# SniperBoard.net
KiCad netlist of a schematic drawn in EAGLE
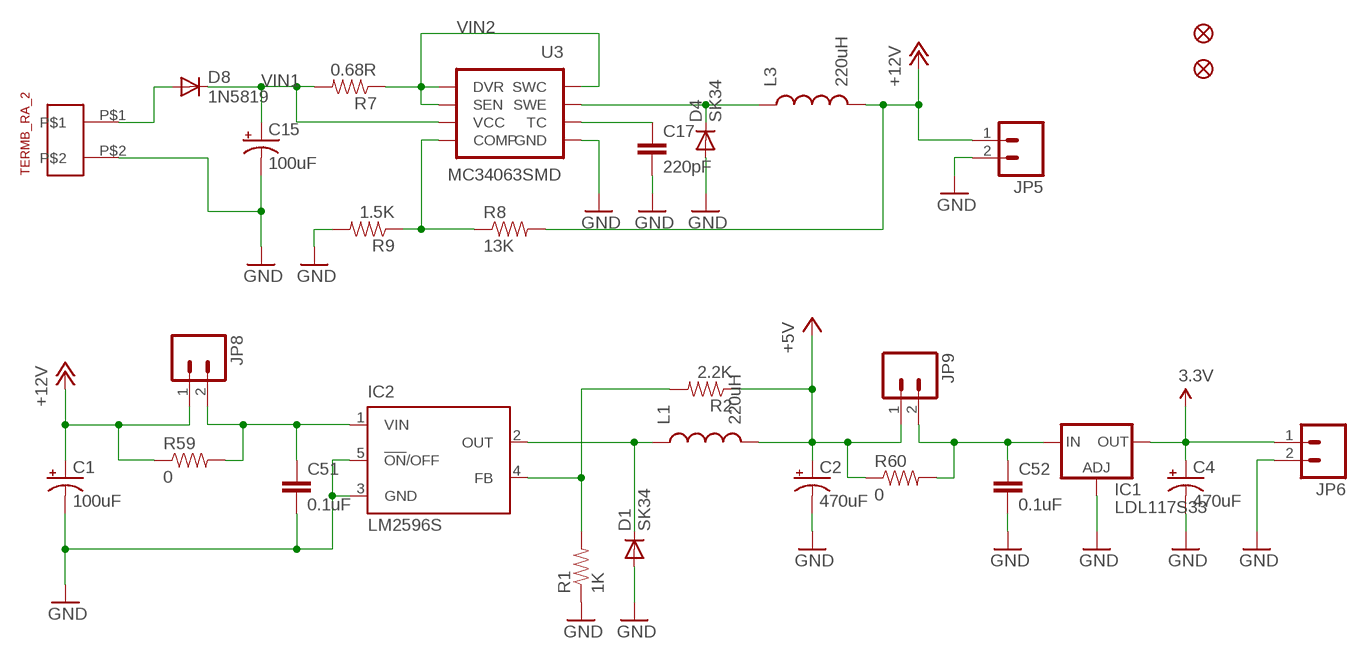
[diagram p0: schematic, sheet 1]
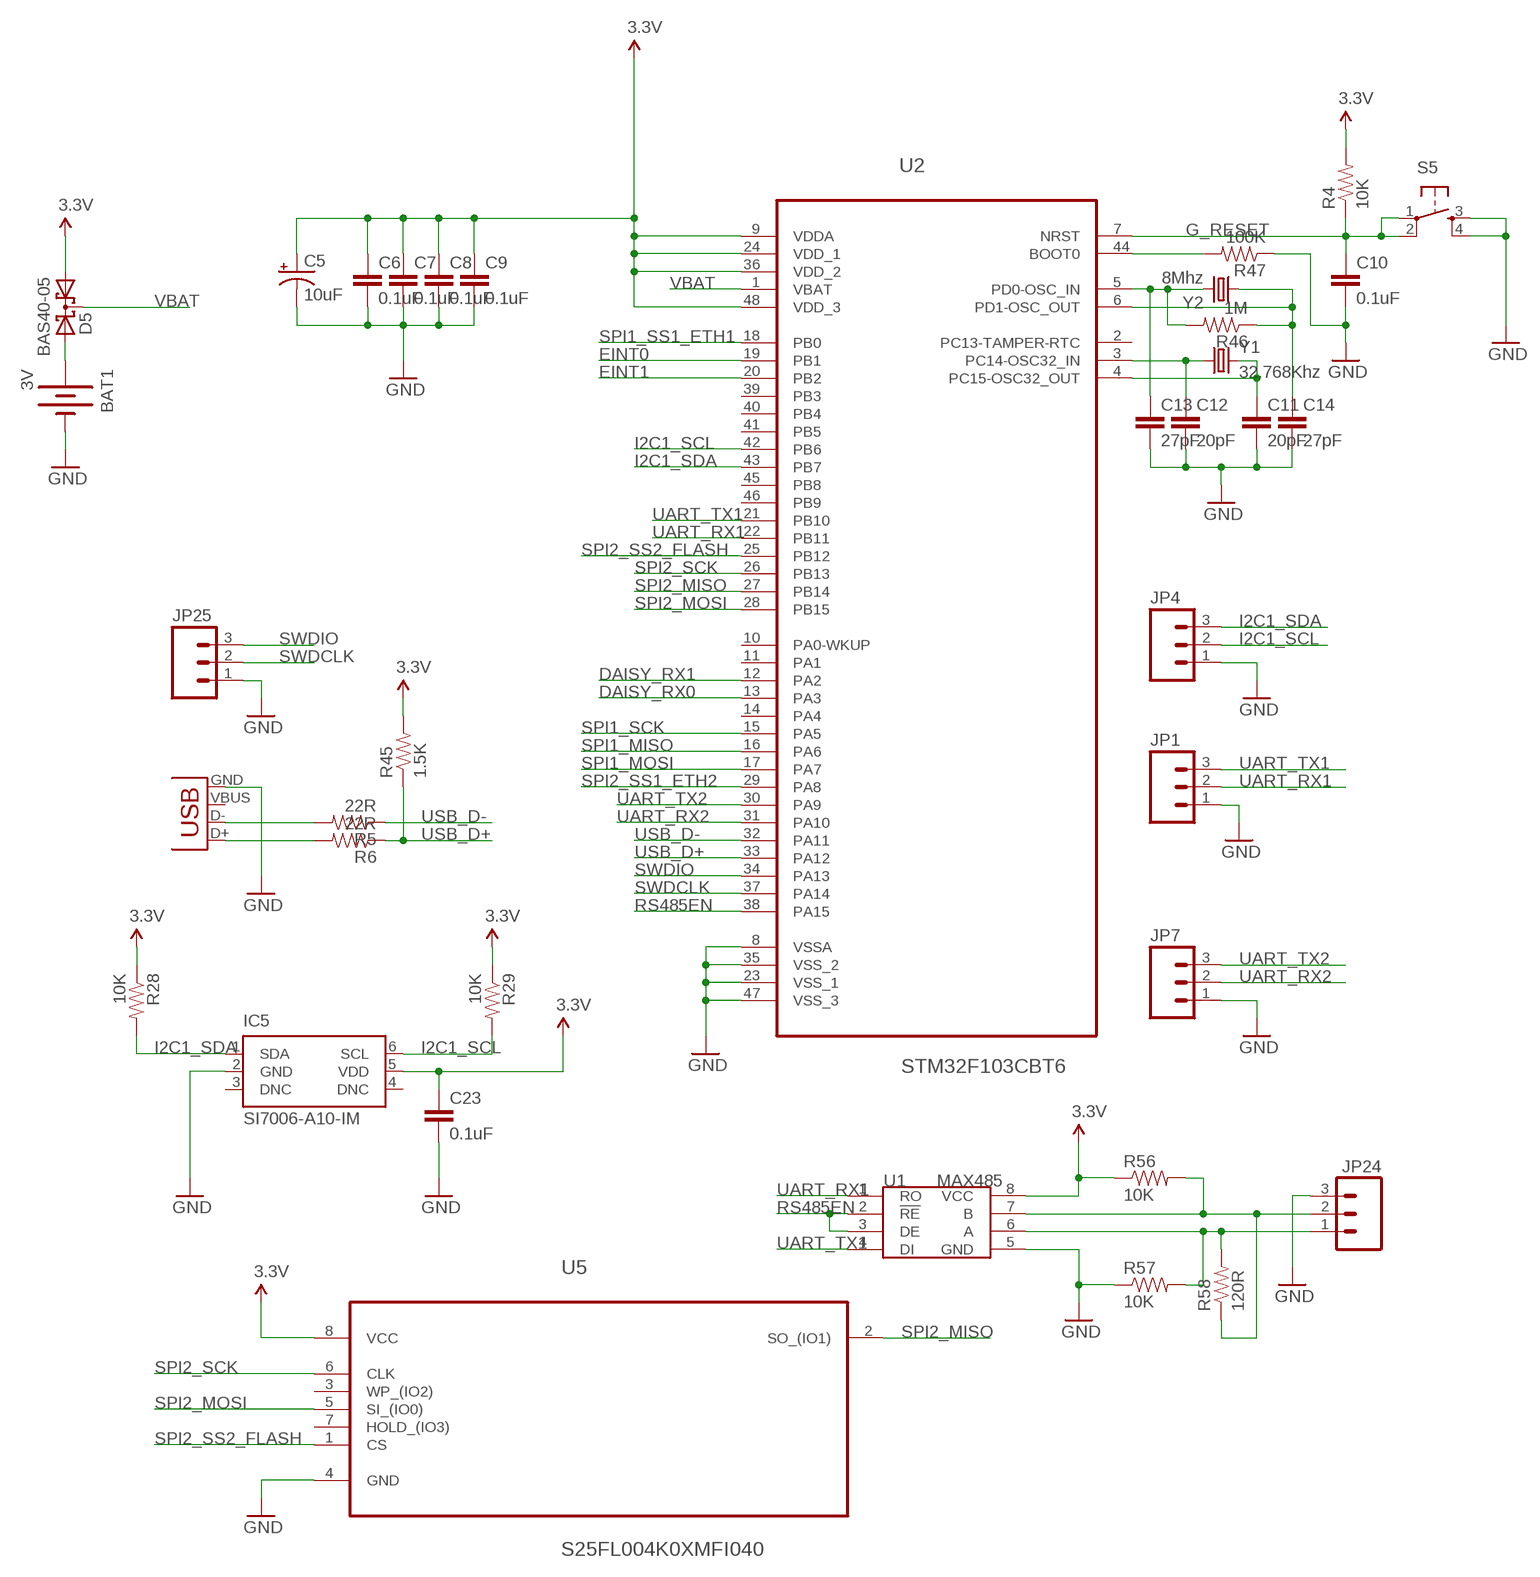
[diagram p1: schematic, sheet 2]
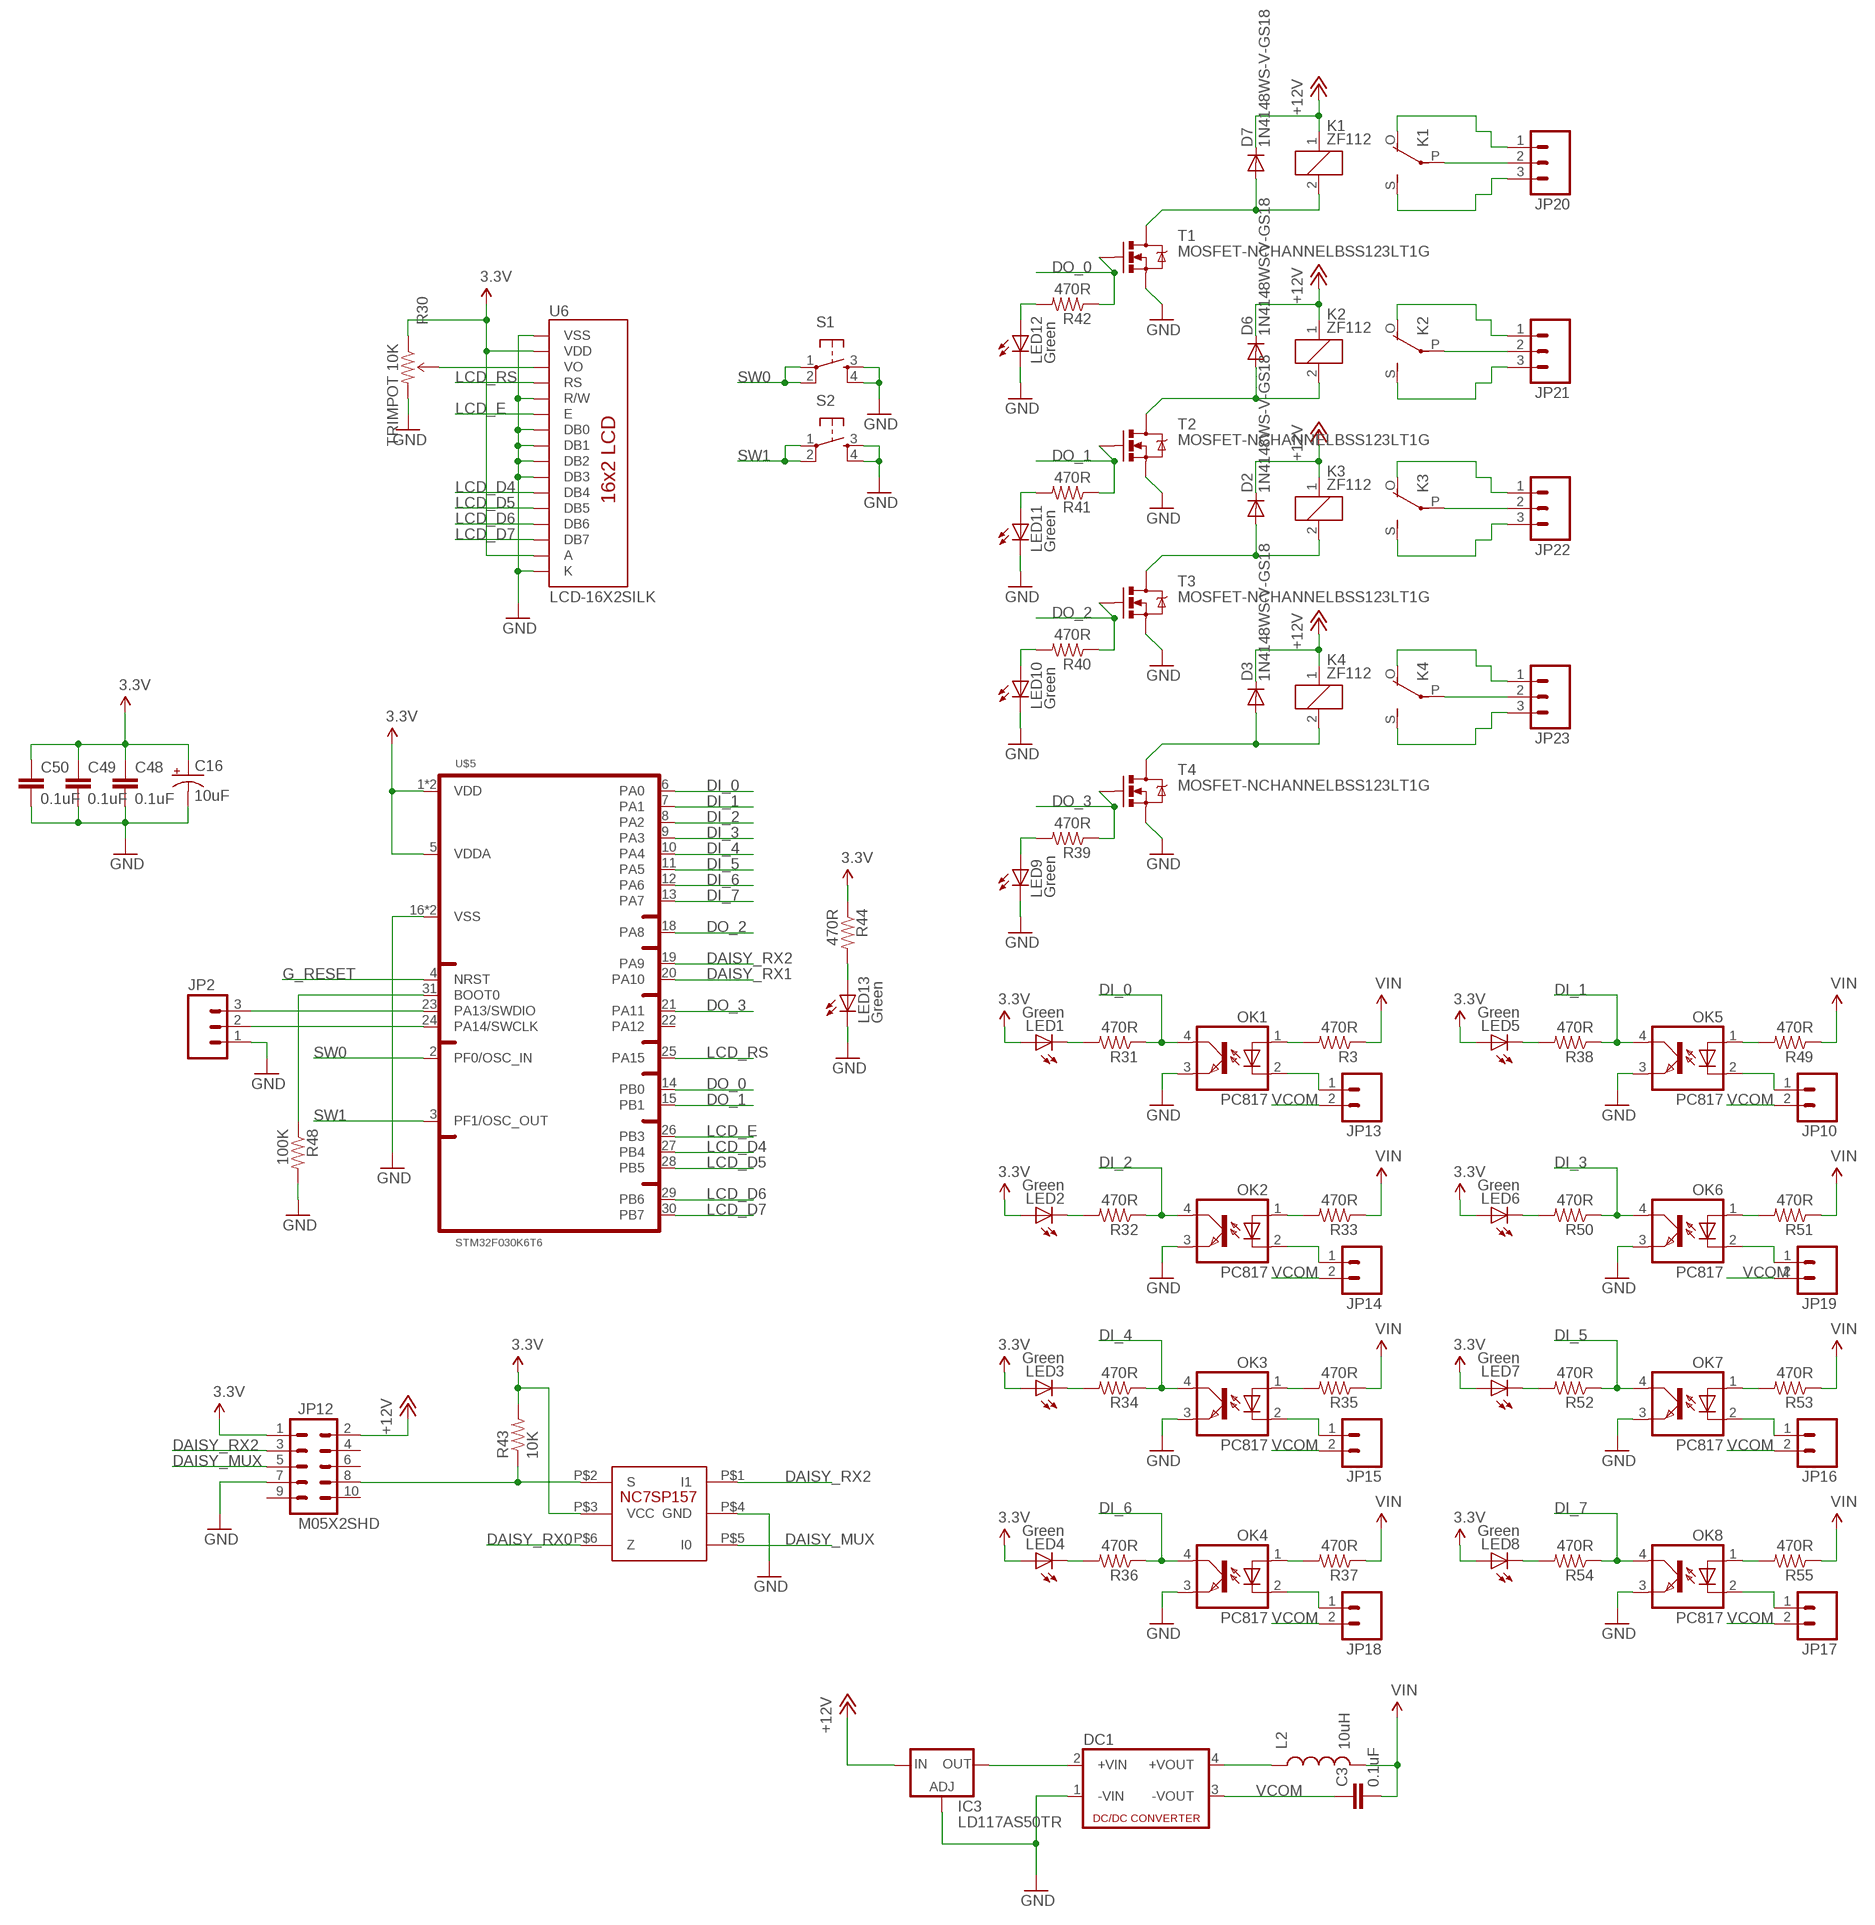
[diagram p2: schematic, sheet 3]
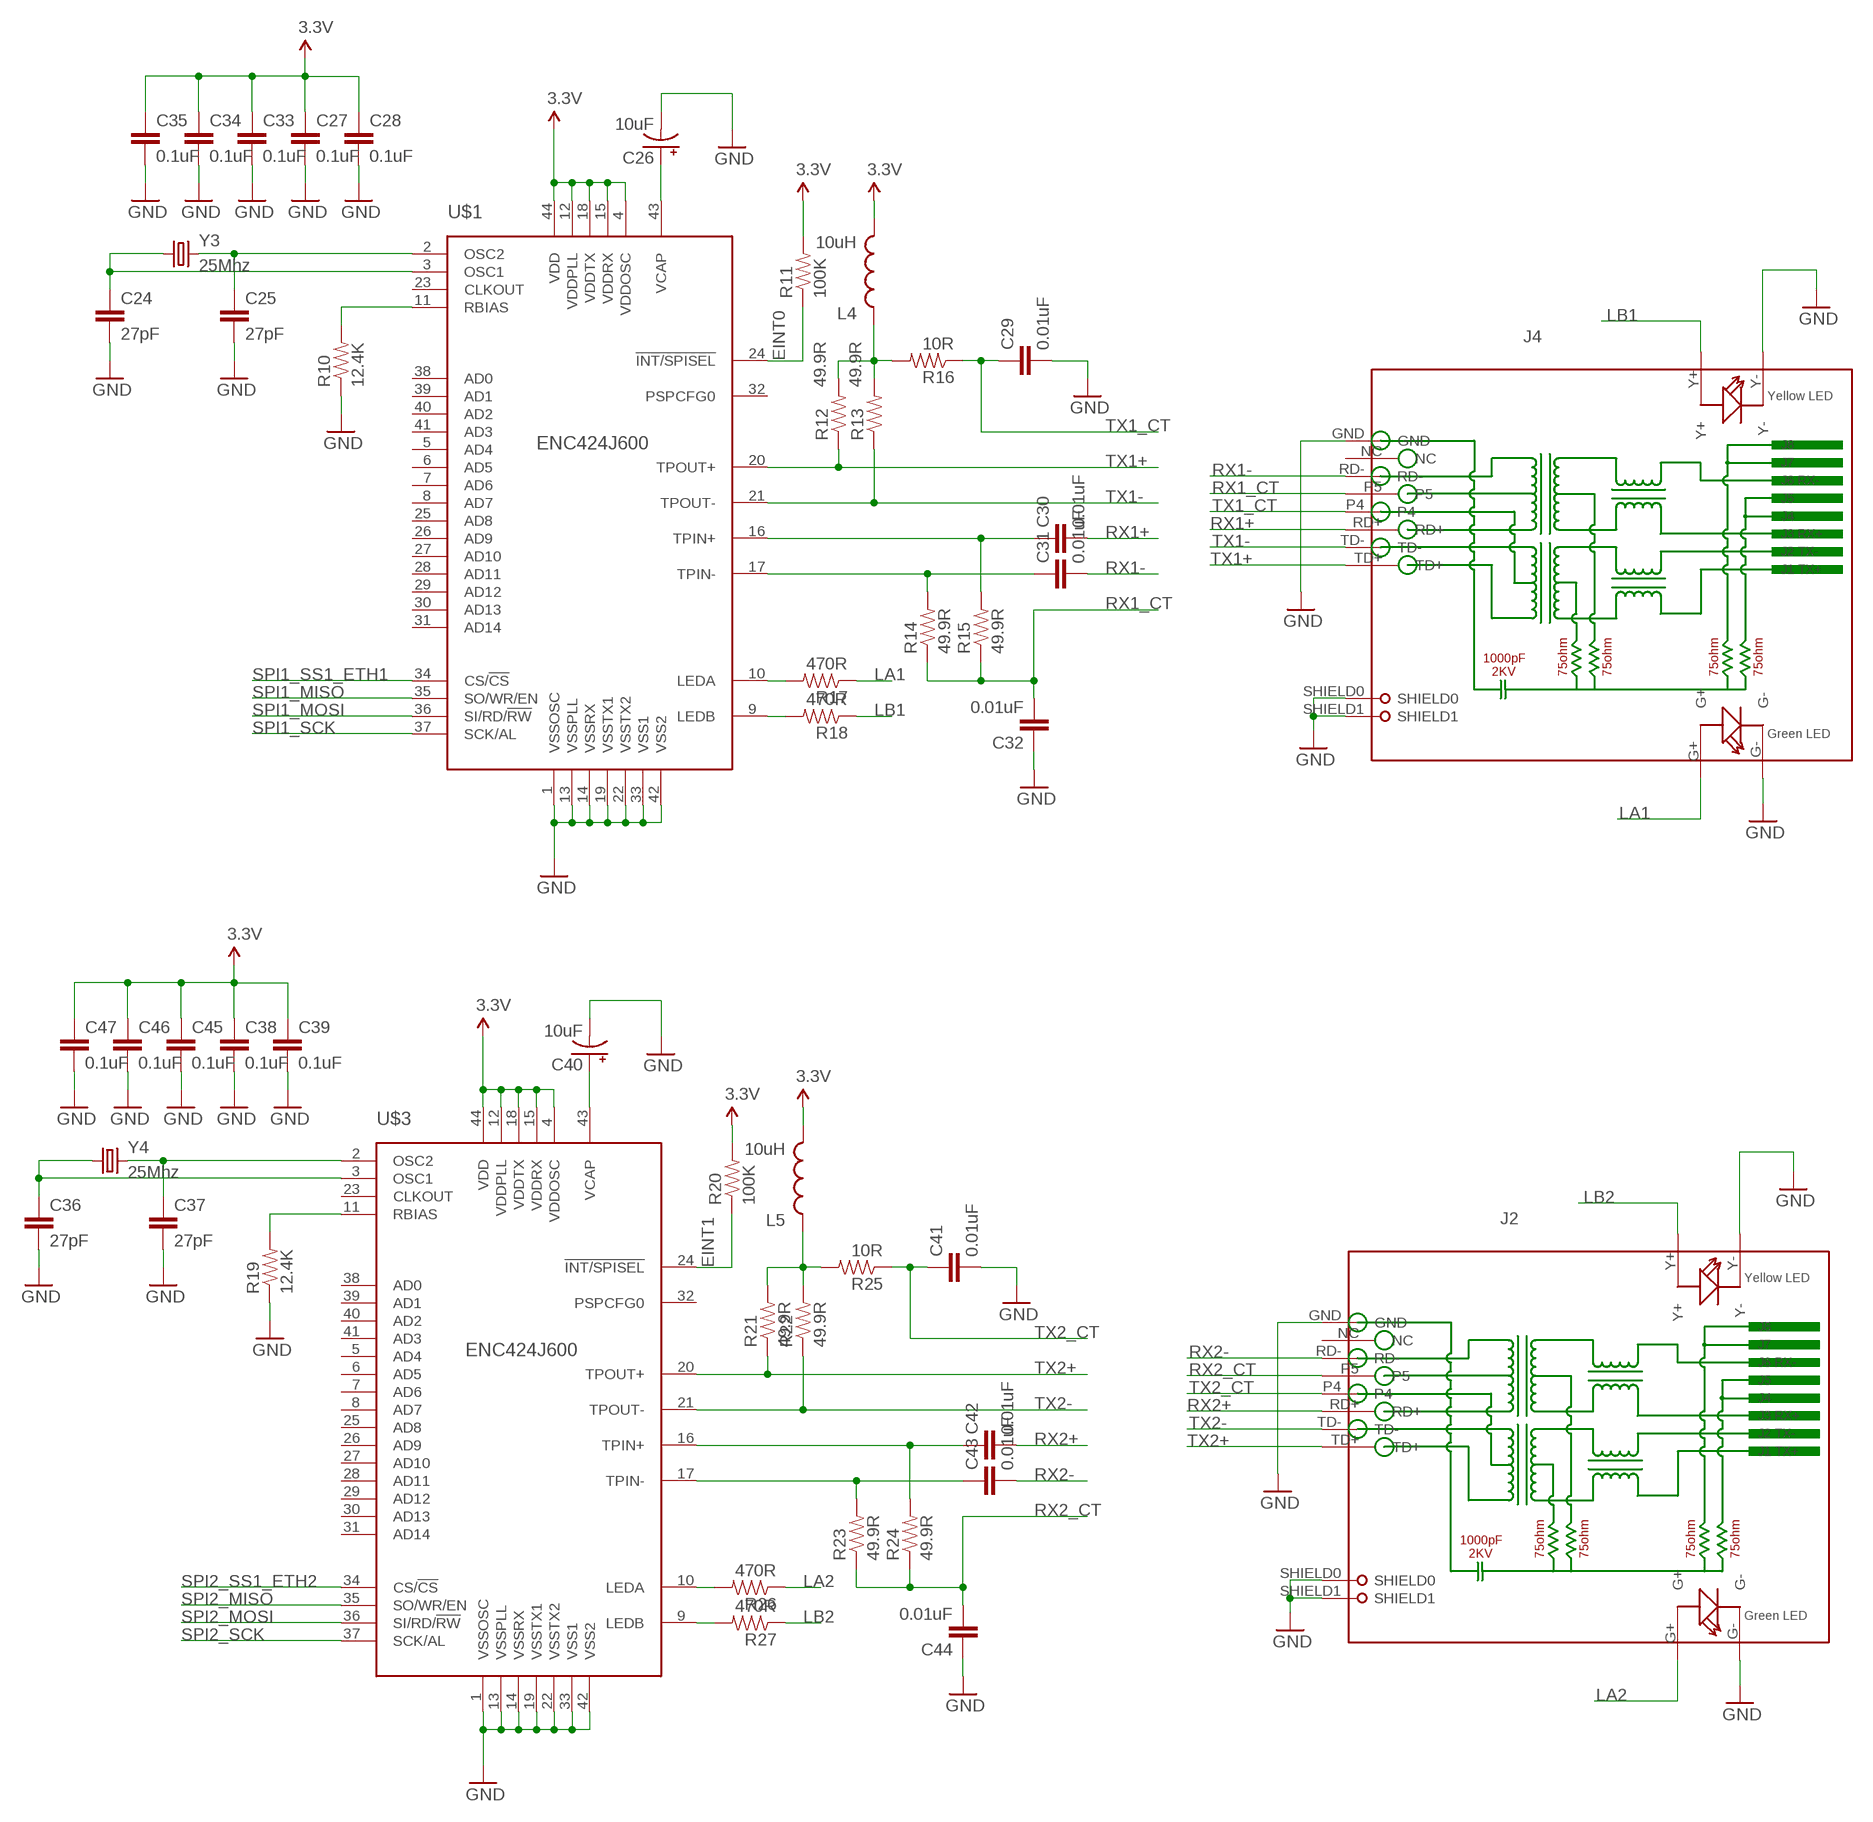
[diagram p3: schematic, sheet 4]
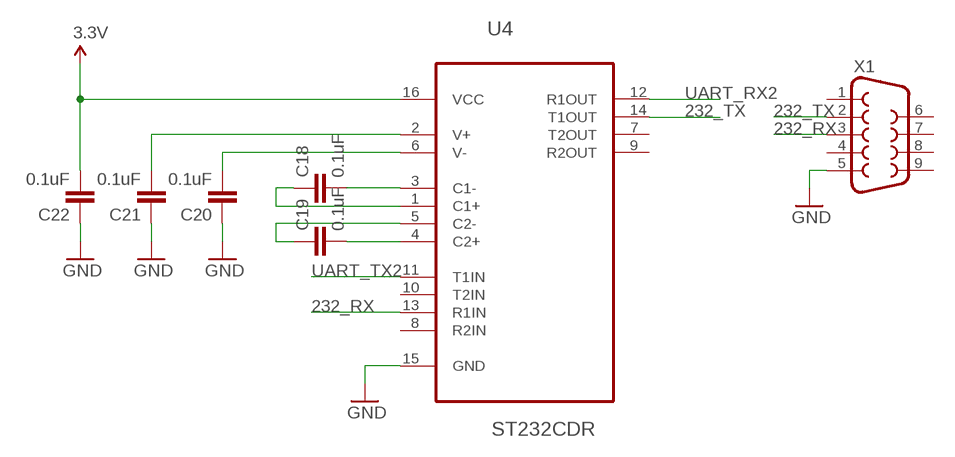
[diagram p4: schematic, sheet 5]

(export (version "E")
  (design (tool "Eeschema 10.0.6"))
  (components
    (comp (ref "C18")
      (value "0.1uF")
      (footprint "eagle-import:0805")
      (libsource (lib "eagle-import") (part "SparkFun-Passives_CAP0805"))
    )
    (comp (ref "C19")
      (value "0.1uF")
      (footprint "eagle-import:0805")
      (libsource (lib "eagle-import") (part "SparkFun-Passives_CAP0805"))
    )
    (comp (ref "C20")
      (value "0.1uF")
      (footprint "eagle-import:0805")
      (libsource (lib "eagle-import") (part "SparkFun-Passives_CAP0805"))
    )
    (comp (ref "C21")
      (value "0.1uF")
      (footprint "eagle-import:0805")
      (libsource (lib "eagle-import") (part "SparkFun-Passives_CAP0805"))
    )
    (comp (ref "C22")
      (value "0.1uF")
      (footprint "eagle-import:0805")
      (libsource (lib "eagle-import") (part "SparkFun-Passives_CAP0805"))
    )
    (comp (ref "U4")
      (value "ST232CDR")
      (footprint "eagle-import:SOIC127P600X175-16N")
      (libsource (lib "eagle-import") (part "ST232CDR"))
    )
    (comp (ref "X1")
      (value "DB9FEMALE")
      (footprint "eagle-import:DB9")
      (libsource (lib "eagle-import") (part "DB9FEMALE"))
    )
    (comp (ref "C24")
      (value "27pF")
      (footprint "eagle-import:0805")
      (libsource (lib "eagle-import") (part "CAP0805"))
    )
    (comp (ref "C25")
      (value "27pF")
      (footprint "eagle-import:0805")
      (libsource (lib "eagle-import") (part "CAP0805"))
    )
    (comp (ref "C26")
      (value "10uF")
      (footprint "eagle-import:EIA3528-KIT")
      (libsource (lib "eagle-import") (part "CAP_POL3528-KIT"))
    )
    (comp (ref "C27")
      (value "0.1uF")
      (footprint "eagle-import:0805")
      (libsource (lib "eagle-import") (part "CAP0805"))
    )
    (comp (ref "C28")
      (value "0.1uF")
      (footprint "eagle-import:0805")
      (libsource (lib "eagle-import") (part "CAP0805"))
    )
    (comp (ref "C29")
      (value "0.01uF")
      (footprint "eagle-import:0805")
      (libsource (lib "eagle-import") (part "CAP0805"))
    )
    (comp (ref "C30")
      (value "0.01uF")
      (footprint "eagle-import:0805")
      (libsource (lib "eagle-import") (part "CAP0805"))
    )
    (comp (ref "C31")
      (value "0.01uF")
      (footprint "eagle-import:0805")
      (libsource (lib "eagle-import") (part "CAP0805"))
    )
    (comp (ref "C32")
      (value "0.01uF")
      (footprint "eagle-import:0805")
      (libsource (lib "eagle-import") (part "CAP0805"))
    )
    (comp (ref "C33")
      (value "0.1uF")
      (footprint "eagle-import:0805")
      (libsource (lib "eagle-import") (part "CAP0805"))
    )
    (comp (ref "C34")
      (value "0.1uF")
      (footprint "eagle-import:0805")
      (libsource (lib "eagle-import") (part "CAP0805"))
    )
    (comp (ref "C35")
      (value "0.1uF")
      (footprint "eagle-import:0805")
      (libsource (lib "eagle-import") (part "CAP0805"))
    )
    (comp (ref "C36")
      (value "27pF")
      (footprint "eagle-import:0805")
      (libsource (lib "eagle-import") (part "CAP0805"))
    )
    (comp (ref "C37")
      (value "27pF")
      (footprint "eagle-import:0805")
      (libsource (lib "eagle-import") (part "CAP0805"))
    )
    (comp (ref "C38")
      (value "0.1uF")
      (footprint "eagle-import:0805")
      (libsource (lib "eagle-import") (part "CAP0805"))
    )
    (comp (ref "C39")
      (value "0.1uF")
      (footprint "eagle-import:0805")
      (libsource (lib "eagle-import") (part "CAP0805"))
    )
    (comp (ref "C40")
      (value "10uF")
      (footprint "eagle-import:EIA3528-KIT")
      (libsource (lib "eagle-import") (part "CAP_POL3528-KIT"))
    )
    (comp (ref "C41")
      (value "0.01uF")
      (footprint "eagle-import:0805")
      (libsource (lib "eagle-import") (part "CAP0805"))
    )
    (comp (ref "C42")
      (value "0.01uF")
      (footprint "eagle-import:0805")
      (libsource (lib "eagle-import") (part "CAP0805"))
    )
    (comp (ref "C43")
      (value "0.01uF")
      (footprint "eagle-import:0805")
      (libsource (lib "eagle-import") (part "CAP0805"))
    )
    (comp (ref "C44")
      (value "0.01uF")
      (footprint "eagle-import:0805")
      (libsource (lib "eagle-import") (part "CAP0805"))
    )
    (comp (ref "C45")
      (value "0.1uF")
      (footprint "eagle-import:0805")
      (libsource (lib "eagle-import") (part "CAP0805"))
    )
    (comp (ref "C46")
      (value "0.1uF")
      (footprint "eagle-import:0805")
      (libsource (lib "eagle-import") (part "CAP0805"))
    )
    (comp (ref "C47")
      (value "0.1uF")
      (footprint "eagle-import:0805")
      (libsource (lib "eagle-import") (part "CAP0805"))
    )
    (comp (ref "J2")
      (value "RJ45-HR911105A-HR911105A")
      (footprint "eagle-import:RJMG1BD3B8K1ANR")
      (libsource (lib "eagle-import") (part "RJ45-HR911105A-HR911105A"))
    )
    (comp (ref "J4")
      (value "RJ45-HR911105A-HR911105A")
      (footprint "eagle-import:RJMG1BD3B8K1ANR")
      (libsource (lib "eagle-import") (part "RJ45-HR911105A-HR911105A"))
    )
    (comp (ref "L4")
      (value "10uH")
      (footprint "eagle-import:0805")
      (libsource (lib "eagle-import") (part "INDUCTOR0805"))
    )
    (comp (ref "L5")
      (value "10uH")
      (footprint "eagle-import:0805")
      (libsource (lib "eagle-import") (part "INDUCTOR0805"))
    )
    (comp (ref "R10")
      (value "12.4K")
      (footprint "eagle-import:0805")
      (libsource (lib "eagle-import") (part "SparkFun-Resistors_RESISTOR0805-RES"))
    )
    (comp (ref "R11")
      (value "100K")
      (footprint "eagle-import:0805")
      (libsource (lib "eagle-import") (part "SparkFun-Resistors_RESISTOR0805-RES"))
    )
    (comp (ref "R12")
      (value "49.9R")
      (footprint "eagle-import:0805")
      (libsource (lib "eagle-import") (part "SparkFun-Resistors_RESISTOR0805-RES"))
    )
    (comp (ref "R13")
      (value "49.9R")
      (footprint "eagle-import:0805")
      (libsource (lib "eagle-import") (part "SparkFun-Resistors_RESISTOR0805-RES"))
    )
    (comp (ref "R14")
      (value "49.9R")
      (footprint "eagle-import:0805")
      (libsource (lib "eagle-import") (part "SparkFun-Resistors_RESISTOR0805-RES"))
    )
    (comp (ref "R15")
      (value "49.9R")
      (footprint "eagle-import:0805")
      (libsource (lib "eagle-import") (part "SparkFun-Resistors_RESISTOR0805-RES"))
    )
    (comp (ref "R16")
      (value "10R")
      (footprint "eagle-import:0805")
      (libsource (lib "eagle-import") (part "SparkFun-Resistors_RESISTOR0805-RES"))
    )
    (comp (ref "R17")
      (value "470R")
      (footprint "eagle-import:0805")
      (libsource (lib "eagle-import") (part "SparkFun-Resistors_RESISTOR0805-RES"))
    )
    (comp (ref "R18")
      (value "470R")
      (footprint "eagle-import:0805")
      (libsource (lib "eagle-import") (part "SparkFun-Resistors_RESISTOR0805-RES"))
    )
    (comp (ref "R19")
      (value "12.4K")
      (footprint "eagle-import:0805")
      (libsource (lib "eagle-import") (part "SparkFun-Resistors_RESISTOR0805-RES"))
    )
    (comp (ref "R20")
      (value "100K")
      (footprint "eagle-import:0805")
      (libsource (lib "eagle-import") (part "SparkFun-Resistors_RESISTOR0805-RES"))
    )
    (comp (ref "R21")
      (value "49.9R")
      (footprint "eagle-import:0805")
      (libsource (lib "eagle-import") (part "SparkFun-Resistors_RESISTOR0805-RES"))
    )
    (comp (ref "R22")
      (value "49.9R")
      (footprint "eagle-import:0805")
      (libsource (lib "eagle-import") (part "SparkFun-Resistors_RESISTOR0805-RES"))
    )
    (comp (ref "R23")
      (value "49.9R")
      (footprint "eagle-import:0805")
      (libsource (lib "eagle-import") (part "SparkFun-Resistors_RESISTOR0805-RES"))
    )
    (comp (ref "R24")
      (value "49.9R")
      (footprint "eagle-import:0805")
      (libsource (lib "eagle-import") (part "SparkFun-Resistors_RESISTOR0805-RES"))
    )
    (comp (ref "R25")
      (value "10R")
      (footprint "eagle-import:0805")
      (libsource (lib "eagle-import") (part "SparkFun-Resistors_RESISTOR0805-RES"))
    )
    (comp (ref "R26")
      (value "470R")
      (footprint "eagle-import:0805")
      (libsource (lib "eagle-import") (part "SparkFun-Resistors_RESISTOR0805-RES"))
    )
    (comp (ref "R27")
      (value "470R")
      (footprint "eagle-import:0805")
      (libsource (lib "eagle-import") (part "SparkFun-Resistors_RESISTOR0805-RES"))
    )
    (comp (ref "U$1")
      (value "ENC424J600")
      (footprint "eagle-import:TQFP-44")
      (libsource (lib "eagle-import") (part "ENC424J600"))
    )
    (comp (ref "U$3")
      (value "ENC424J600")
      (footprint "eagle-import:TQFP-44")
      (libsource (lib "eagle-import") (part "ENC424J600"))
    )
    (comp (ref "Y3")
      (value "25Mhz")
      (footprint "eagle-import:CRYSTAL-SMD-10.5X4.8-2PIN")
      (libsource (lib "eagle-import") (part "CRYSTAL10.5X4.8"))
    )
    (comp (ref "Y4")
      (value "25Mhz")
      (footprint "eagle-import:CRYSTAL-SMD-10.5X4.8-2PIN")
      (libsource (lib "eagle-import") (part "CRYSTAL10.5X4.8"))
    )
    (comp (ref "C3")
      (value "0.1uF")
      (footprint "eagle-import:0805")
      (libsource (lib "eagle-import") (part "CAP0805"))
    )
    (comp (ref "C16")
      (value "10uF")
      (footprint "eagle-import:EIA3216")
      (libsource (lib "eagle-import") (part "10UF-TANT"))
    )
    (comp (ref "C48")
      (value "0.1uF")
      (footprint "eagle-import:0805")
      (libsource (lib "eagle-import") (part "CAP0805"))
    )
    (comp (ref "C49")
      (value "0.1uF")
      (footprint "eagle-import:0805")
      (libsource (lib "eagle-import") (part "CAP0805"))
    )
    (comp (ref "C50")
      (value "0.1uF")
      (footprint "eagle-import:0805")
      (libsource (lib "eagle-import") (part "CAP0805"))
    )
    (comp (ref "D2")
      (value "1N4148WS-V-GS18")
      (footprint "eagle-import:SMA-DIODE_ALT")
      (libsource (lib "eagle-import") (part "DIODESMA-ALT"))
    )
    (comp (ref "D3")
      (value "1N4148WS-V-GS18")
      (footprint "eagle-import:SMA-DIODE_ALT")
      (libsource (lib "eagle-import") (part "DIODESMA-ALT"))
    )
    (comp (ref "D6")
      (value "1N4148WS-V-GS18")
      (footprint "eagle-import:SMA-DIODE_ALT")
      (libsource (lib "eagle-import") (part "DIODESMA-ALT"))
    )
    (comp (ref "D7")
      (value "1N4148WS-V-GS18")
      (footprint "eagle-import:SMA-DIODE_ALT")
      (libsource (lib "eagle-import") (part "DIODESMA-ALT"))
    )
    (comp (ref "DC1")
      (value "NME")
      (footprint "eagle-import:NME")
      (fields (field (name "MF") "C & D TECHNOLOGIES, INC") (field (name "MPN") "NME1205D"))
      (libsource (lib "eagle-import") (part "NME"))
    )
    (comp (ref "IC3")
      (value "LD117AS50TR")
      (footprint "eagle-import:SOT223")
      (libsource (lib "eagle-import") (part "LD117A?S50TR"))
    )
    (comp (ref "JP2")
      (value "M03POLAR")
      (footprint "eagle-import:MOLEX-1X3")
      (libsource (lib "eagle-import") (part "M03POLAR"))
    )
    (comp (ref "JP10")
      (value "M025MM")
      (footprint "eagle-import:SCREWTERMINAL-5MM-2")
      (libsource (lib "eagle-import") (part "M025MM"))
    )
    (comp (ref "JP12")
      (value "M05X2SHD")
      (footprint "eagle-import:2X5-SHROUDED")
      (libsource (lib "eagle-import") (part "M05X2SHD"))
    )
    (comp (ref "JP13")
      (value "M025MM")
      (footprint "eagle-import:SCREWTERMINAL-5MM-2")
      (libsource (lib "eagle-import") (part "M025MM"))
    )
    (comp (ref "JP14")
      (value "M025MM")
      (footprint "eagle-import:SCREWTERMINAL-5MM-2")
      (libsource (lib "eagle-import") (part "M025MM"))
    )
    (comp (ref "JP15")
      (value "M025MM")
      (footprint "eagle-import:SCREWTERMINAL-5MM-2")
      (libsource (lib "eagle-import") (part "M025MM"))
    )
    (comp (ref "JP16")
      (value "M025MM")
      (footprint "eagle-import:SCREWTERMINAL-5MM-2")
      (libsource (lib "eagle-import") (part "M025MM"))
    )
    (comp (ref "JP17")
      (value "M025MM")
      (footprint "eagle-import:SCREWTERMINAL-5MM-2")
      (libsource (lib "eagle-import") (part "M025MM"))
    )
    (comp (ref "JP18")
      (value "M025MM")
      (footprint "eagle-import:SCREWTERMINAL-5MM-2")
      (libsource (lib "eagle-import") (part "M025MM"))
    )
    (comp (ref "JP19")
      (value "M025MM")
      (footprint "eagle-import:SCREWTERMINAL-5MM-2")
      (libsource (lib "eagle-import") (part "M025MM"))
    )
    (comp (ref "JP20")
      (value "M03-SCREW-5MM")
      (footprint "eagle-import:SCREWTERMINAL-5MM-3")
      (libsource (lib "eagle-import") (part "M03-SCREW-5MM"))
    )
    (comp (ref "JP21")
      (value "M03-SCREW-5MM")
      (footprint "eagle-import:SCREWTERMINAL-5MM-3")
      (libsource (lib "eagle-import") (part "M03-SCREW-5MM"))
    )
    (comp (ref "JP22")
      (value "M03-SCREW-5MM")
      (footprint "eagle-import:SCREWTERMINAL-5MM-3")
      (libsource (lib "eagle-import") (part "M03-SCREW-5MM"))
    )
    (comp (ref "JP23")
      (value "M03-SCREW-5MM")
      (footprint "eagle-import:SCREWTERMINAL-5MM-3")
      (libsource (lib "eagle-import") (part "M03-SCREW-5MM"))
    )
    (comp (ref "K1")
      (value "ZF112")
      (footprint "eagle-import:ZF112")
      (libsource (lib "eagle-import") (part "ZF112"))
    )
    (comp (ref "K2")
      (value "ZF112")
      (footprint "eagle-import:ZF112")
      (libsource (lib "eagle-import") (part "ZF112"))
    )
    (comp (ref "K3")
      (value "ZF112")
      (footprint "eagle-import:ZF112")
      (libsource (lib "eagle-import") (part "ZF112"))
    )
    (comp (ref "K4")
      (value "ZF112")
      (footprint "eagle-import:ZF112")
      (libsource (lib "eagle-import") (part "ZF112"))
    )
    (comp (ref "L2")
      (value "10uH")
      (footprint "eagle-import:0805")
      (libsource (lib "eagle-import") (part "INDUCTOR0805"))
    )
    (comp (ref "LED1")
      (value "Green")
      (footprint "eagle-import:LED-1206")
      (libsource (lib "eagle-import") (part "LED1206"))
    )
    (comp (ref "LED2")
      (value "Green")
      (footprint "eagle-import:LED-1206")
      (libsource (lib "eagle-import") (part "LED1206"))
    )
    (comp (ref "LED3")
      (value "Green")
      (footprint "eagle-import:LED-1206")
      (libsource (lib "eagle-import") (part "LED1206"))
    )
    (comp (ref "LED4")
      (value "Green")
      (footprint "eagle-import:LED-1206")
      (libsource (lib "eagle-import") (part "LED1206"))
    )
    (comp (ref "LED5")
      (value "Green")
      (footprint "eagle-import:LED-1206")
      (libsource (lib "eagle-import") (part "LED1206"))
    )
    (comp (ref "LED6")
      (value "Green")
      (footprint "eagle-import:LED-1206")
      (libsource (lib "eagle-import") (part "LED1206"))
    )
    (comp (ref "LED7")
      (value "Green")
      (footprint "eagle-import:LED-1206")
      (libsource (lib "eagle-import") (part "LED1206"))
    )
    (comp (ref "LED8")
      (value "Green")
      (footprint "eagle-import:LED-1206")
      (libsource (lib "eagle-import") (part "LED1206"))
    )
    (comp (ref "LED9")
      (value "Green")
      (footprint "eagle-import:LED-1206")
      (libsource (lib "eagle-import") (part "LED1206"))
    )
    (comp (ref "LED10")
      (value "Green")
      (footprint "eagle-import:LED-1206")
      (libsource (lib "eagle-import") (part "LED1206"))
    )
    (comp (ref "LED11")
      (value "Green")
      (footprint "eagle-import:LED-1206")
      (libsource (lib "eagle-import") (part "LED1206"))
    )
    (comp (ref "LED12")
      (value "Green")
      (footprint "eagle-import:LED-1206")
      (libsource (lib "eagle-import") (part "LED1206"))
    )
    (comp (ref "LED13")
      (value "Green")
      (footprint "eagle-import:LED-1206")
      (libsource (lib "eagle-import") (part "LED1206"))
    )
    (comp (ref "OK1")
      (value "PC817")
      (footprint "eagle-import:DIL04")
      (fields (field (name "MPN") "PC817X4J000F"))
      (libsource (lib "eagle-import") (part "PC817"))
    )
    (comp (ref "OK2")
      (value "PC817")
      (footprint "eagle-import:DIL04")
      (fields (field (name "MPN") "PC817X4J000F"))
      (libsource (lib "eagle-import") (part "PC817"))
    )
    (comp (ref "OK3")
      (value "PC817")
      (footprint "eagle-import:DIL04")
      (fields (field (name "MPN") "PC817X4J000F"))
      (libsource (lib "eagle-import") (part "PC817"))
    )
    (comp (ref "OK4")
      (value "PC817")
      (footprint "eagle-import:DIL04")
      (fields (field (name "MPN") "PC817X4J000F"))
      (libsource (lib "eagle-import") (part "PC817"))
    )
    (comp (ref "OK5")
      (value "PC817")
      (footprint "eagle-import:DIL04")
      (fields (field (name "MPN") "PC817X4J000F"))
      (libsource (lib "eagle-import") (part "PC817"))
    )
    (comp (ref "OK6")
      (value "PC817")
      (footprint "eagle-import:DIL04")
      (fields (field (name "MPN") "PC817X4J000F"))
      (libsource (lib "eagle-import") (part "PC817"))
    )
    (comp (ref "OK7")
      (value "PC817")
      (footprint "eagle-import:DIL04")
      (fields (field (name "MPN") "PC817X4J000F"))
      (libsource (lib "eagle-import") (part "PC817"))
    )
    (comp (ref "OK8")
      (value "PC817")
      (footprint "eagle-import:DIL04")
      (fields (field (name "MPN") "PC817X4J000F"))
      (libsource (lib "eagle-import") (part "PC817"))
    )
    (comp (ref "R3")
      (value "470R")
      (footprint "eagle-import:0805")
      (libsource (lib "eagle-import") (part "RESISTOR0805-RES"))
    )
    (comp (ref "R30")
      (value "TRIMPOT 10K")
      (footprint "eagle-import:TRIM_POT_PTH")
      (libsource (lib "eagle-import") (part "TRIMPOTPTH"))
    )
    (comp (ref "R31")
      (value "470R")
      (footprint "eagle-import:0805")
      (libsource (lib "eagle-import") (part "RESISTOR0805-RES"))
    )
    (comp (ref "R32")
      (value "470R")
      (footprint "eagle-import:0805")
      (libsource (lib "eagle-import") (part "RESISTOR0805-RES"))
    )
    (comp (ref "R33")
      (value "470R")
      (footprint "eagle-import:0805")
      (libsource (lib "eagle-import") (part "RESISTOR0805-RES"))
    )
    (comp (ref "R34")
      (value "470R")
      (footprint "eagle-import:0805")
      (libsource (lib "eagle-import") (part "RESISTOR0805-RES"))
    )
    (comp (ref "R35")
      (value "470R")
      (footprint "eagle-import:0805")
      (libsource (lib "eagle-import") (part "RESISTOR0805-RES"))
    )
    (comp (ref "R36")
      (value "470R")
      (footprint "eagle-import:0805")
      (libsource (lib "eagle-import") (part "RESISTOR0805-RES"))
    )
    (comp (ref "R37")
      (value "470R")
      (footprint "eagle-import:0805")
      (libsource (lib "eagle-import") (part "RESISTOR0805-RES"))
    )
    (comp (ref "R38")
      (value "470R")
      (footprint "eagle-import:0805")
      (libsource (lib "eagle-import") (part "RESISTOR0805-RES"))
    )
    (comp (ref "R39")
      (value "470R")
      (footprint "eagle-import:0805")
      (libsource (lib "eagle-import") (part "RESISTOR0805-RES"))
    )
    (comp (ref "R40")
      (value "470R")
      (footprint "eagle-import:0805")
      (libsource (lib "eagle-import") (part "RESISTOR0805-RES"))
    )
    (comp (ref "R41")
      (value "470R")
      (footprint "eagle-import:0805")
      (libsource (lib "eagle-import") (part "RESISTOR0805-RES"))
    )
    (comp (ref "R42")
      (value "470R")
      (footprint "eagle-import:0805")
      (libsource (lib "eagle-import") (part "RESISTOR0805-RES"))
    )
    (comp (ref "R43")
      (value "10K")
      (footprint "eagle-import:0805")
      (libsource (lib "eagle-import") (part "RESISTOR0805-RES"))
    )
    (comp (ref "R44")
      (value "470R")
      (footprint "eagle-import:0805")
      (libsource (lib "eagle-import") (part "RESISTOR0805-RES"))
    )
    (comp (ref "R48")
      (value "100K")
      (footprint "eagle-import:0805")
      (libsource (lib "eagle-import") (part "RESISTOR0805-RES"))
    )
    (comp (ref "R49")
      (value "470R")
      (footprint "eagle-import:0805")
      (libsource (lib "eagle-import") (part "RESISTOR0805-RES"))
    )
    (comp (ref "R50")
      (value "470R")
      (footprint "eagle-import:0805")
      (libsource (lib "eagle-import") (part "RESISTOR0805-RES"))
    )
    (comp (ref "R51")
      (value "470R")
      (footprint "eagle-import:0805")
      (libsource (lib "eagle-import") (part "RESISTOR0805-RES"))
    )
    (comp (ref "R52")
      (value "470R")
      (footprint "eagle-import:0805")
      (libsource (lib "eagle-import") (part "RESISTOR0805-RES"))
    )
    (comp (ref "R53")
      (value "470R")
      (footprint "eagle-import:0805")
      (libsource (lib "eagle-import") (part "RESISTOR0805-RES"))
    )
    (comp (ref "R54")
      (value "470R")
      (footprint "eagle-import:0805")
      (libsource (lib "eagle-import") (part "RESISTOR0805-RES"))
    )
    (comp (ref "R55")
      (value "470R")
      (footprint "eagle-import:0805")
      (libsource (lib "eagle-import") (part "RESISTOR0805-RES"))
    )
    (comp (ref "S1")
      (value "TAC_SWITCHPTH")
      (footprint "eagle-import:TACTILE-PTH")
      (libsource (lib "eagle-import") (part "TAC_SWITCHPTH"))
    )
    (comp (ref "S2")
      (value "TAC_SWITCHPTH")
      (footprint "eagle-import:TACTILE-PTH")
      (libsource (lib "eagle-import") (part "TAC_SWITCHPTH"))
    )
    (comp (ref "T1")
      (value "MOSFET-NCHANNELBSS123LT1G")
      (footprint "eagle-import:SOT23")
      (libsource (lib "eagle-import") (part "MOSFET-NCHANNELBSS123LT1G"))
    )
    (comp (ref "T2")
      (value "MOSFET-NCHANNELBSS123LT1G")
      (footprint "eagle-import:SOT23")
      (libsource (lib "eagle-import") (part "MOSFET-NCHANNELBSS123LT1G"))
    )
    (comp (ref "T3")
      (value "MOSFET-NCHANNELBSS123LT1G")
      (footprint "eagle-import:SOT23")
      (libsource (lib "eagle-import") (part "MOSFET-NCHANNELBSS123LT1G"))
    )
    (comp (ref "T4")
      (value "MOSFET-NCHANNELBSS123LT1G")
      (footprint "eagle-import:SOT23")
      (libsource (lib "eagle-import") (part "MOSFET-NCHANNELBSS123LT1G"))
    )
    (comp (ref "U$4")
      (value "NC7SP157")
      (footprint "eagle-import:SC70-6")
      (libsource (lib "eagle-import") (part "NC7SP157"))
    )
    (comp (ref "U$5")
      (value "STM32F030K6T6")
      (footprint "eagle-import:LQFP32-7X7")
      (libsource (lib "eagle-import") (part "STM32F030K6T6"))
    )
    (comp (ref "U6")
      (value "LCD-16X2SILK")
      (footprint "eagle-import:LCD-16X2")
      (libsource (lib "eagle-import") (part "LCD-16X2SILK"))
    )
    (comp (ref "C1")
      (value "100uF")
      (footprint "eagle-import:PANASONIC_E")
      (libsource (lib "eagle-import") (part "CAP_POLE"))
    )
    (comp (ref "C2")
      (value "470uF")
      (footprint "eagle-import:PANASONIC_E")
      (libsource (lib "eagle-import") (part "CAP_POLE"))
    )
    (comp (ref "C4")
      (value "470uF")
      (footprint "eagle-import:PANASONIC_E")
      (libsource (lib "eagle-import") (part "CAP_POLE"))
    )
    (comp (ref "C15")
      (value "100uF")
      (footprint "eagle-import:PANASONIC_E")
      (libsource (lib "eagle-import") (part "CAP_POLE"))
    )
    (comp (ref "C17")
      (value "220pF")
      (footprint "eagle-import:0805")
      (libsource (lib "eagle-import") (part "SparkFun-Passives_CAP0805"))
    )
    (comp (ref "C51")
      (value "0.1uF")
      (footprint "eagle-import:0805")
      (libsource (lib "eagle-import") (part "CAP0805"))
    )
    (comp (ref "C52")
      (value "0.1uF")
      (footprint "eagle-import:0805")
      (libsource (lib "eagle-import") (part "CAP0805"))
    )
    (comp (ref "D1")
      (value "SK34")
      (footprint "eagle-import:SMA-DIODE")
      (libsource (lib "eagle-import") (part "DIODESMA"))
    )
    (comp (ref "D4")
      (value "SK34")
      (footprint "eagle-import:SMA-DIODE")
      (libsource (lib "eagle-import") (part "DIODESMA"))
    )
    (comp (ref "D8")
      (value "1N5819")
      (footprint "eagle-import:SMB-DIODE")
      (libsource (lib "eagle-import") (part "DIODESMB"))
    )
    (comp (ref "FID1")
      (value "FIDUCIAL1.5X3")
      (footprint "eagle-import:FIDUCIAL-1.5X3")
      (libsource (lib "eagle-import") (part "FIDUCIAL1.5X3"))
    )
    (comp (ref "FID2")
      (value "FIDUCIAL1.5X3")
      (footprint "eagle-import:FIDUCIAL-1.5X3")
      (libsource (lib "eagle-import") (part "FIDUCIAL1.5X3"))
    )
    (comp (ref "IC1")
      (value "LDL117S33")
      (footprint "eagle-import:DPACK")
      (libsource (lib "eagle-import") (part "LD117A?DT12TR"))
    )
    (comp (ref "IC2")
      (value "LM2596S")
      (footprint "eagle-import:TO263-5")
      (fields (field (name "MF") "NATIONAL SEMICONDUCTOR") (field (name "MPN") "LM2596S-ADJ/NOPB"))
      (libsource (lib "eagle-import") (part "LM2596S"))
    )
    (comp (ref "JP5")
      (value "M02POLAR")
      (footprint "eagle-import:MOLEX-1X2")
      (libsource (lib "eagle-import") (part "M02POLAR"))
    )
    (comp (ref "JP6")
      (value "M02POLAR")
      (footprint "eagle-import:MOLEX-1X2")
      (libsource (lib "eagle-import") (part "M02POLAR"))
    )
    (comp (ref "JP8")
      (value "M02PTH")
      (footprint "eagle-import:1X02")
      (libsource (lib "eagle-import") (part "M02PTH"))
    )
    (comp (ref "JP9")
      (value "M02PTH")
      (footprint "eagle-import:1X02")
      (libsource (lib "eagle-import") (part "M02PTH"))
    )
    (comp (ref "L1")
      (value "220uH")
      (footprint "eagle-import:RLB914-IND")
      (libsource (lib "eagle-import") (part "INDUCTORRADIAL5MM"))
    )
    (comp (ref "L3")
      (value "220uH")
      (footprint "eagle-import:RLB914-IND")
      (libsource (lib "eagle-import") (part "INDUCTORRADIAL5MM"))
    )
    (comp (ref "R1")
      (value "1K")
      (footprint "eagle-import:0805")
      (libsource (lib "eagle-import") (part "RESISTOR0805-RES"))
    )
    (comp (ref "R2")
      (value "2.2K")
      (footprint "eagle-import:0805")
      (libsource (lib "eagle-import") (part "RESISTOR0805-RES"))
    )
    (comp (ref "R7")
      (value "0.68R")
      (footprint "eagle-import:0805")
      (libsource (lib "eagle-import") (part "RESISTOR0805-RES"))
    )
    (comp (ref "R8")
      (value "13K")
      (footprint "eagle-import:0805")
      (libsource (lib "eagle-import") (part "RESISTOR0805-RES"))
    )
    (comp (ref "R9")
      (value "1.5K")
      (footprint "eagle-import:0805")
      (libsource (lib "eagle-import") (part "RESISTOR0805-RES"))
    )
    (comp (ref "R59")
      (value "0")
      (footprint "eagle-import:0805")
      (libsource (lib "eagle-import") (part "RESISTOR0805-RES"))
    )
    (comp (ref "R60")
      (value "0")
      (footprint "eagle-import:0805")
      (libsource (lib "eagle-import") (part "RESISTOR0805-RES"))
    )
    (comp (ref "U$2")
      (value "1X02_TERMB_RA")
      (footprint "eagle-import:1X02_TERMB_RA")
      (libsource (lib "eagle-import") (part "1X02_TERMB_RA"))
    )
    (comp (ref "U3")
      (value "MC34063SMD")
      (footprint "eagle-import:SO08")
      (libsource (lib "eagle-import") (part "MC34063SMD"))
    )
    (comp (ref "BAT1")
      (value "3V")
      (footprint "eagle-import:BATTCOM_20MM_PTH")
      (libsource (lib "eagle-import") (part "BATTERY20PTH"))
    )
    (comp (ref "C5")
      (value "10uF")
      (footprint "eagle-import:EIA3216")
      (libsource (lib "eagle-import") (part "10UF-TANT"))
    )
    (comp (ref "C6")
      (value "0.1uF")
      (footprint "eagle-import:0805")
      (libsource (lib "eagle-import") (part "CAP0805"))
    )
    (comp (ref "C7")
      (value "0.1uF")
      (footprint "eagle-import:0805")
      (libsource (lib "eagle-import") (part "CAP0805"))
    )
    (comp (ref "C8")
      (value "0.1uF")
      (footprint "eagle-import:0805")
      (libsource (lib "eagle-import") (part "CAP0805"))
    )
    (comp (ref "C9")
      (value "0.1uF")
      (footprint "eagle-import:0805")
      (libsource (lib "eagle-import") (part "CAP0805"))
    )
    (comp (ref "C10")
      (value "0.1uF")
      (footprint "eagle-import:0805")
      (libsource (lib "eagle-import") (part "CAP0805"))
    )
    (comp (ref "C11")
      (value "20pF")
      (footprint "eagle-import:0805")
      (libsource (lib "eagle-import") (part "CAP0805"))
    )
    (comp (ref "C12")
      (value "20pF")
      (footprint "eagle-import:0805")
      (libsource (lib "eagle-import") (part "CAP0805"))
    )
    (comp (ref "C13")
      (value "27pF")
      (footprint "eagle-import:0805")
      (libsource (lib "eagle-import") (part "CAP0805"))
    )
    (comp (ref "C14")
      (value "27pF")
      (footprint "eagle-import:0805")
      (libsource (lib "eagle-import") (part "CAP0805"))
    )
    (comp (ref "C23")
      (value "0.1uF")
      (footprint "eagle-import:0805")
      (libsource (lib "eagle-import") (part "CAP0805"))
    )
    (comp (ref "D5")
      (value "BAS40-05")
      (footprint "eagle-import:SOT23")
      (libsource (lib "eagle-import") (part "BAS40-05"))
    )
    (comp (ref "IC5")
      (value "SI7006-A10-IM")
      (footprint "eagle-import:DFN6-3X3")
      (fields (field (name "MF") "Silicon Labs") (field (name "MPN") "Si7006-A10-IM"))
      (libsource (lib "eagle-import") (part "SI7006-A10-IM"))
    )
    (comp (ref "JP1")
      (value "M03PTH")
      (footprint "eagle-import:1X03")
      (libsource (lib "eagle-import") (part "M03PTH"))
    )
    (comp (ref "JP3")
      (value "USB-B")
      (footprint "eagle-import:USB-B-PTH")
      (libsource (lib "eagle-import") (part "USBPTH"))
    )
    (comp (ref "JP4")
      (value "M03PTH")
      (footprint "eagle-import:1X03")
      (libsource (lib "eagle-import") (part "M03PTH"))
    )
    (comp (ref "JP7")
      (value "M03PTH")
      (footprint "eagle-import:1X03")
      (libsource (lib "eagle-import") (part "M03PTH"))
    )
    (comp (ref "JP24")
      (value "M03-SCREW-5MM")
      (footprint "eagle-import:SCREWTERMINAL-5MM-3")
      (libsource (lib "eagle-import") (part "M03-SCREW-5MM"))
    )
    (comp (ref "JP25")
      (value "M03POLAR")
      (footprint "eagle-import:MOLEX-1X3")
      (libsource (lib "eagle-import") (part "M03POLAR"))
    )
    (comp (ref "R4")
      (value "10K")
      (footprint "eagle-import:0805")
      (libsource (lib "eagle-import") (part "SparkFun-Resistors_RESISTOR0805-RES"))
    )
    (comp (ref "R5")
      (value "22R")
      (footprint "eagle-import:0805")
      (libsource (lib "eagle-import") (part "SparkFun-Resistors_RESISTOR0805-RES"))
    )
    (comp (ref "R6")
      (value "22R")
      (footprint "eagle-import:0805")
      (libsource (lib "eagle-import") (part "SparkFun-Resistors_RESISTOR0805-RES"))
    )
    (comp (ref "R28")
      (value "10K")
      (footprint "eagle-import:0805")
      (libsource (lib "eagle-import") (part "SparkFun-Resistors_RESISTOR0805-RES"))
    )
    (comp (ref "R29")
      (value "10K")
      (footprint "eagle-import:0805")
      (libsource (lib "eagle-import") (part "SparkFun-Resistors_RESISTOR0805-RES"))
    )
    (comp (ref "R45")
      (value "1.5K")
      (footprint "eagle-import:0805")
      (libsource (lib "eagle-import") (part "SparkFun-Resistors_RESISTOR0805-RES"))
    )
    (comp (ref "R46")
      (value "1M")
      (footprint "eagle-import:0805")
      (libsource (lib "eagle-import") (part "SparkFun-Resistors_RESISTOR0805-RES"))
    )
    (comp (ref "R47")
      (value "100K")
      (footprint "eagle-import:0805")
      (libsource (lib "eagle-import") (part "SparkFun-Resistors_RESISTOR0805-RES"))
    )
    (comp (ref "R56")
      (value "10K")
      (footprint "eagle-import:0805")
      (libsource (lib "eagle-import") (part "SparkFun-Resistors_RESISTOR0805-RES"))
    )
    (comp (ref "R57")
      (value "10K")
      (footprint "eagle-import:0805")
      (libsource (lib "eagle-import") (part "SparkFun-Resistors_RESISTOR0805-RES"))
    )
    (comp (ref "R58")
      (value "120R")
      (footprint "eagle-import:1206")
      (libsource (lib "eagle-import") (part "SparkFun-Resistors_RESISTOR1206"))
    )
    (comp (ref "S5")
      (value "TAC_SWITCHPTH")
      (footprint "eagle-import:TACTILE-PTH")
      (libsource (lib "eagle-import") (part "TAC_SWITCHPTH"))
    )
    (comp (ref "U1")
      (value "MAX485")
      (footprint "eagle-import:SOP8")
      (libsource (lib "eagle-import") (part "MAX485"))
    )
    (comp (ref "U2")
      (value "STM32F103CBT6")
      (footprint "eagle-import:QFP50P900X900X160-48N")
      (libsource (lib "eagle-import") (part "STM32F103CBT6"))
    )
    (comp (ref "U5")
      (value "S25FL004K0XMFI040")
      (footprint "eagle-import:SOIC127P600X175-8N")
      (libsource (lib "eagle-import") (part "S25FL004K0XMFI040"))
    )
    (comp (ref "Y1")
      (value "32.768Khz")
      (footprint "eagle-import:MC-306")
      (fields (field (name "MPN") "MC-306 60.0KHZ  100PPM ,12.5PF"))
      (libsource (lib "eagle-import") (part "MC-306"))
    )
    (comp (ref "Y2")
      (value "8Mhz")
      (footprint "eagle-import:HC49US")
      (libsource (lib "eagle-import") (part "CRYSTALHC49US"))
    )
  )
  (nets
    (net (code "1") (name "+5V") (class "Default")
      (node (ref "C2") (pin "+") (pinfunction "+_+") (pintype "passive"))
      (node (ref "JP9") (pin "1") (pinfunction "1_1") (pintype "passive"))
      (node (ref "L1") (pin "P$2") (pinfunction "2_P$2") (pintype "passive"))
      (node (ref "R2") (pin "1") (pinfunction "1_1") (pintype "passive"))
      (node (ref "R60") (pin "1") (pinfunction "1_1") (pintype "passive"))
    )
    (net (code "2") (name "+12V") (class "Default")
      (node (ref "C1") (pin "+") (pinfunction "+_+") (pintype "passive"))
      (node (ref "D2") (pin "C") (pinfunction "C_C") (pintype "passive"))
      (node (ref "D3") (pin "C") (pinfunction "C_C") (pintype "passive"))
      (node (ref "D6") (pin "C") (pinfunction "C_C") (pintype "passive"))
      (node (ref "D7") (pin "C") (pinfunction "C_C") (pintype "passive"))
      (node (ref "IC3") (pin "3") (pinfunction "IN_3") (pintype "input"))
      (node (ref "JP12") (pin "2") (pinfunction "2_2") (pintype "passive"))
      (node (ref "JP5") (pin "1") (pinfunction "1_1") (pintype "passive"))
      (node (ref "JP8") (pin "1") (pinfunction "1_1") (pintype "passive"))
      (node (ref "K1") (pin "1") (pinfunction "1_1") (pintype "passive"))
      (node (ref "K2") (pin "1") (pinfunction "1_1") (pintype "passive"))
      (node (ref "K3") (pin "1") (pinfunction "1_1") (pintype "passive"))
      (node (ref "K4") (pin "1") (pinfunction "1_1") (pintype "passive"))
      (node (ref "L3") (pin "P$2") (pinfunction "2_P$2") (pintype "passive"))
      (node (ref "R59") (pin "1") (pinfunction "1_1") (pintype "passive"))
      (node (ref "R8") (pin "2") (pinfunction "2_2") (pintype "passive"))
    )
    (net (code "3") (name "3.3V") (class "Default")
      (node (ref "C16") (pin "A") (pinfunction "+_A") (pintype "passive"))
      (node (ref "C22") (pin "2") (pinfunction "2_2") (pintype "passive"))
      (node (ref "C23") (pin "1") (pinfunction "1_1") (pintype "passive"))
      (node (ref "C27") (pin "1") (pinfunction "1_1") (pintype "passive"))
      (node (ref "C28") (pin "1") (pinfunction "1_1") (pintype "passive"))
      (node (ref "C33") (pin "1") (pinfunction "1_1") (pintype "passive"))
      (node (ref "C34") (pin "1") (pinfunction "1_1") (pintype "passive"))
      (node (ref "C35") (pin "1") (pinfunction "1_1") (pintype "passive"))
      (node (ref "C38") (pin "1") (pinfunction "1_1") (pintype "passive"))
      (node (ref "C39") (pin "1") (pinfunction "1_1") (pintype "passive"))
      (node (ref "C4") (pin "+") (pinfunction "+_+") (pintype "passive"))
      (node (ref "C45") (pin "1") (pinfunction "1_1") (pintype "passive"))
      (node (ref "C46") (pin "1") (pinfunction "1_1") (pintype "passive"))
      (node (ref "C47") (pin "1") (pinfunction "1_1") (pintype "passive"))
      (node (ref "C48") (pin "1") (pinfunction "1_1") (pintype "passive"))
      (node (ref "C49") (pin "1") (pinfunction "1_1") (pintype "passive"))
      (node (ref "C5") (pin "A") (pinfunction "+_A") (pintype "passive"))
      (node (ref "C50") (pin "1") (pinfunction "1_1") (pintype "passive"))
      (node (ref "C6") (pin "1") (pinfunction "1_1") (pintype "passive"))
      (node (ref "C7") (pin "1") (pinfunction "1_1") (pintype "passive"))
      (node (ref "C8") (pin "1") (pinfunction "1_1") (pintype "passive"))
      (node (ref "C9") (pin "1") (pinfunction "1_1") (pintype "passive"))
      (node (ref "D5") (pin "1") (pinfunction "A1_1") (pintype "passive"))
      (node (ref "IC1") (pin "4") (pinfunction "OUT_4") (pintype "passive"))
      (node (ref "IC5") (pin "5") (pinfunction "VDD_5") (pintype "power_in"))
      (node (ref "JP12") (pin "1") (pinfunction "1_1") (pintype "passive"))
      (node (ref "JP6") (pin "1") (pinfunction "1_1") (pintype "passive"))
      (node (ref "L4") (pin "2") (pinfunction "2_2") (pintype "passive"))
      (node (ref "L5") (pin "2") (pinfunction "2_2") (pintype "passive"))
      (node (ref "LED1") (pin "A") (pinfunction "A_A") (pintype "passive"))
      (node (ref "LED2") (pin "A") (pinfunction "A_A") (pintype "passive"))
      (node (ref "LED3") (pin "A") (pinfunction "A_A") (pintype "passive"))
      (node (ref "LED4") (pin "A") (pinfunction "A_A") (pintype "passive"))
      (node (ref "LED5") (pin "A") (pinfunction "A_A") (pintype "passive"))
      (node (ref "LED6") (pin "A") (pinfunction "A_A") (pintype "passive"))
      (node (ref "LED7") (pin "A") (pinfunction "A_A") (pintype "passive"))
      (node (ref "LED8") (pin "A") (pinfunction "A_A") (pintype "passive"))
      (node (ref "R11") (pin "2") (pinfunction "2_2") (pintype "passive"))
      (node (ref "R20") (pin "2") (pinfunction "2_2") (pintype "passive"))
      (node (ref "R28") (pin "1") (pinfunction "1_1") (pintype "passive"))
      (node (ref "R29") (pin "1") (pinfunction "1_1") (pintype "passive"))
      (node (ref "R30") (pin "1") (pinfunction "CCW_1") (pintype "passive"))
      (node (ref "R4") (pin "2") (pinfunction "2_2") (pintype "passive"))
      (node (ref "R43") (pin "2") (pinfunction "2_2") (pintype "passive"))
      (node (ref "R44") (pin "1") (pinfunction "1_1") (pintype "passive"))
      (node (ref "R45") (pin "2") (pinfunction "2_2") (pintype "passive"))
      (node (ref "R56") (pin "1") (pinfunction "1_1") (pintype "passive"))
      (node (ref "U$1") (pin "12") (pinfunction "VDDPLL_12") (pintype "bidirectional"))
      (node (ref "U$1") (pin "15") (pinfunction "VDDRX_15") (pintype "bidirectional"))
      (node (ref "U$1") (pin "18") (pinfunction "VDDTX_18") (pintype "bidirectional"))
      (node (ref "U$1") (pin "4") (pinfunction "VDDOSC_4") (pintype "bidirectional"))
      (node (ref "U$1") (pin "44") (pinfunction "VDD_44") (pintype "bidirectional"))
      (node (ref "U$3") (pin "12") (pinfunction "VDDPLL_12") (pintype "bidirectional"))
      (node (ref "U$3") (pin "15") (pinfunction "VDDRX_15") (pintype "bidirectional"))
      (node (ref "U$3") (pin "18") (pinfunction "VDDTX_18") (pintype "bidirectional"))
      (node (ref "U$3") (pin "4") (pinfunction "VDDOSC_4") (pintype "bidirectional"))
      (node (ref "U$3") (pin "44") (pinfunction "VDD_44") (pintype "bidirectional"))
      (node (ref "U$4") (pin "P$3") (pinfunction "VCC_P$3") (pintype "bidirectional"))
      (node (ref "U$5") (pin "1") (pinfunction "VDD_1") (pintype "bidirectional"))
      (node (ref "U$5") (pin "17") (pinfunction "VDD_17") (pintype "bidirectional"))
      (node (ref "U$5") (pin "5") (pinfunction "VDDA_5") (pintype "bidirectional"))
      (node (ref "U1") (pin "8") (pinfunction "VCC_8") (pintype "bidirectional"))
      (node (ref "U2") (pin "24") (pinfunction "VDD_1_24") (pintype "bidirectional"))
      (node (ref "U2") (pin "36") (pinfunction "VDD_2_36") (pintype "power_in"))
      (node (ref "U2") (pin "48") (pinfunction "VDD_3_48") (pintype "power_in"))
      (node (ref "U2") (pin "9") (pinfunction "VDDA_9") (pintype "power_in"))
      (node (ref "U4") (pin "16") (pinfunction "VCC_16") (pintype "power_in"))
      (node (ref "U5") (pin "8") (pinfunction "VCC_8") (pintype "power_in"))
      (node (ref "U6") (pin "15") (pinfunction "A_15") (pintype "power_in"))
      (node (ref "U6") (pin "2") (pinfunction "VDD_2") (pintype "power_in"))
    )
    (net (code "4") (name "232_RX") (class "Default")
      (node (ref "U4") (pin "13") (pinfunction "R1IN_13") (pintype "input"))
      (node (ref "X1") (pin "3") (pinfunction "3_3") (pintype "passive"))
    )
    (net (code "5") (name "232_TX") (class "Default")
      (node (ref "U4") (pin "14") (pinfunction "T1OUT_14") (pintype "output"))
      (node (ref "X1") (pin "2") (pinfunction "2_2") (pintype "passive"))
    )
    (net (code "6") (name "DAISY_MUX") (class "Default")
      (node (ref "JP12") (pin "5") (pinfunction "5_5") (pintype "passive"))
      (node (ref "U$4") (pin "P$5") (pinfunction "I0_P$5") (pintype "bidirectional"))
    )
    (net (code "7") (name "DAISY_RX0") (class "Default")
      (node (ref "U$4") (pin "P$6") (pinfunction "Z_P$6") (pintype "bidirectional"))
      (node (ref "U2") (pin "13") (pinfunction "PA3_13") (pintype "bidirectional"))
    )
    (net (code "8") (name "DAISY_RX1") (class "Default")
      (node (ref "U$5") (pin "20") (pinfunction "PA10_20") (pintype "bidirectional"))
      (node (ref "U2") (pin "12") (pinfunction "PA2_12") (pintype "bidirectional"))
    )
    (net (code "9") (name "DAISY_RX2") (class "Default")
      (node (ref "JP12") (pin "3") (pinfunction "3_3") (pintype "passive"))
      (node (ref "U$4") (pin "P$1") (pinfunction "I1_P$1") (pintype "bidirectional"))
      (node (ref "U$5") (pin "19") (pinfunction "PA9_19") (pintype "bidirectional"))
    )
    (net (code "10") (name "DI_0") (class "Default")
      (node (ref "OK1") (pin "4") (pinfunction "COL_4") (pintype "passive"))
      (node (ref "R31") (pin "1") (pinfunction "1_1") (pintype "passive"))
      (node (ref "U$5") (pin "6") (pinfunction "PA0_6") (pintype "bidirectional"))
    )
    (net (code "11") (name "DI_1") (class "Default")
      (node (ref "OK5") (pin "4") (pinfunction "COL_4") (pintype "passive"))
      (node (ref "R38") (pin "1") (pinfunction "1_1") (pintype "passive"))
      (node (ref "U$5") (pin "7") (pinfunction "PA1_7") (pintype "bidirectional"))
    )
    (net (code "12") (name "DI_2") (class "Default")
      (node (ref "OK2") (pin "4") (pinfunction "COL_4") (pintype "passive"))
      (node (ref "R32") (pin "1") (pinfunction "1_1") (pintype "passive"))
      (node (ref "U$5") (pin "8") (pinfunction "PA2_8") (pintype "bidirectional"))
    )
    (net (code "13") (name "DI_3") (class "Default")
      (node (ref "OK6") (pin "4") (pinfunction "COL_4") (pintype "passive"))
      (node (ref "R50") (pin "1") (pinfunction "1_1") (pintype "passive"))
      (node (ref "U$5") (pin "9") (pinfunction "PA3_9") (pintype "bidirectional"))
    )
    (net (code "14") (name "DI_4") (class "Default")
      (node (ref "OK3") (pin "4") (pinfunction "COL_4") (pintype "passive"))
      (node (ref "R34") (pin "1") (pinfunction "1_1") (pintype "passive"))
      (node (ref "U$5") (pin "10") (pinfunction "PA4_10") (pintype "bidirectional"))
    )
    (net (code "15") (name "DI_5") (class "Default")
      (node (ref "OK7") (pin "4") (pinfunction "COL_4") (pintype "passive"))
      (node (ref "R52") (pin "1") (pinfunction "1_1") (pintype "passive"))
      (node (ref "U$5") (pin "11") (pinfunction "PA5_11") (pintype "bidirectional"))
    )
    (net (code "16") (name "DI_6") (class "Default")
      (node (ref "OK4") (pin "4") (pinfunction "COL_4") (pintype "passive"))
      (node (ref "R36") (pin "1") (pinfunction "1_1") (pintype "passive"))
      (node (ref "U$5") (pin "12") (pinfunction "PA6_12") (pintype "bidirectional"))
    )
    (net (code "17") (name "DI_7") (class "Default")
      (node (ref "OK8") (pin "4") (pinfunction "COL_4") (pintype "passive"))
      (node (ref "R54") (pin "1") (pinfunction "1_1") (pintype "passive"))
      (node (ref "U$5") (pin "13") (pinfunction "PA7_13") (pintype "bidirectional"))
    )
    (net (code "18") (name "DO_0") (class "Default")
      (node (ref "R42") (pin "1") (pinfunction "1_1") (pintype "passive"))
      (node (ref "T1") (pin "1") (pinfunction "G_1") (pintype "passive"))
      (node (ref "U$5") (pin "14") (pinfunction "PB0_14") (pintype "bidirectional"))
    )
    (net (code "19") (name "DO_1") (class "Default")
      (node (ref "R41") (pin "1") (pinfunction "1_1") (pintype "passive"))
      (node (ref "T2") (pin "1") (pinfunction "G_1") (pintype "passive"))
      (node (ref "U$5") (pin "15") (pinfunction "PB1_15") (pintype "bidirectional"))
    )
    (net (code "20") (name "DO_2") (class "Default")
      (node (ref "R40") (pin "1") (pinfunction "1_1") (pintype "passive"))
      (node (ref "T3") (pin "1") (pinfunction "G_1") (pintype "passive"))
      (node (ref "U$5") (pin "18") (pinfunction "PA8_18") (pintype "bidirectional"))
    )
    (net (code "21") (name "DO_3") (class "Default")
      (node (ref "R39") (pin "1") (pinfunction "1_1") (pintype "passive"))
      (node (ref "T4") (pin "1") (pinfunction "G_1") (pintype "passive"))
      (node (ref "U$5") (pin "21") (pinfunction "PA11_21") (pintype "bidirectional"))
    )
    (net (code "22") (name "EINT0") (class "Default")
      (node (ref "R11") (pin "1") (pinfunction "1_1") (pintype "passive"))
      (node (ref "U$1") (pin "24") (pinfunction "~{INT/SPISEL}_24") (pintype "bidirectional"))
      (node (ref "U2") (pin "19") (pinfunction "PB1_19") (pintype "bidirectional"))
    )
    (net (code "23") (name "EINT1") (class "Default")
      (node (ref "R20") (pin "1") (pinfunction "1_1") (pintype "passive"))
      (node (ref "U$3") (pin "24") (pinfunction "~{INT/SPISEL}_24") (pintype "bidirectional"))
      (node (ref "U2") (pin "20") (pinfunction "PB2_20") (pintype "bidirectional"))
    )
    (net (code "24") (name "GND") (class "Default")
      (node (ref "BAT1") (pin "2") (pinfunction "-_2") (pintype "power_in"))
      (node (ref "C1") (pin "-") (pinfunction "-_-") (pintype "passive"))
      (node (ref "C10") (pin "2") (pinfunction "2_2") (pintype "passive"))
      (node (ref "C11") (pin "2") (pinfunction "2_2") (pintype "passive"))
      (node (ref "C12") (pin "2") (pinfunction "2_2") (pintype "passive"))
      (node (ref "C13") (pin "2") (pinfunction "2_2") (pintype "passive"))
      (node (ref "C14") (pin "2") (pinfunction "2_2") (pintype "passive"))
      (node (ref "C15") (pin "-") (pinfunction "-_-") (pintype "passive"))
      (node (ref "C16") (pin "C") (pinfunction "-_C") (pintype "passive"))
      (node (ref "C17") (pin "2") (pinfunction "2_2") (pintype "passive"))
      (node (ref "C2") (pin "-") (pinfunction "-_-") (pintype "passive"))
      (node (ref "C20") (pin "1") (pinfunction "1_1") (pintype "passive"))
      (node (ref "C21") (pin "1") (pinfunction "1_1") (pintype "passive"))
      (node (ref "C22") (pin "1") (pinfunction "1_1") (pintype "passive"))
      (node (ref "C23") (pin "2") (pinfunction "2_2") (pintype "passive"))
      (node (ref "C24") (pin "2") (pinfunction "2_2") (pintype "passive"))
      (node (ref "C25") (pin "2") (pinfunction "2_2") (pintype "passive"))
      (node (ref "C26") (pin "C") (pinfunction "-_C") (pintype "passive"))
      (node (ref "C27") (pin "2") (pinfunction "2_2") (pintype "passive"))
      (node (ref "C28") (pin "2") (pinfunction "2_2") (pintype "passive"))
      (node (ref "C29") (pin "2") (pinfunction "2_2") (pintype "passive"))
      (node (ref "C32") (pin "1") (pinfunction "1_1") (pintype "passive"))
      (node (ref "C33") (pin "2") (pinfunction "2_2") (pintype "passive"))
      (node (ref "C34") (pin "2") (pinfunction "2_2") (pintype "passive"))
      (node (ref "C35") (pin "2") (pinfunction "2_2") (pintype "passive"))
      (node (ref "C36") (pin "2") (pinfunction "2_2") (pintype "passive"))
      (node (ref "C37") (pin "2") (pinfunction "2_2") (pintype "passive"))
      (node (ref "C38") (pin "2") (pinfunction "2_2") (pintype "passive"))
      (node (ref "C39") (pin "2") (pinfunction "2_2") (pintype "passive"))
      (node (ref "C4") (pin "-") (pinfunction "-_-") (pintype "passive"))
      (node (ref "C40") (pin "C") (pinfunction "-_C") (pintype "passive"))
      (node (ref "C41") (pin "2") (pinfunction "2_2") (pintype "passive"))
      (node (ref "C44") (pin "1") (pinfunction "1_1") (pintype "passive"))
      (node (ref "C45") (pin "2") (pinfunction "2_2") (pintype "passive"))
      (node (ref "C46") (pin "2") (pinfunction "2_2") (pintype "passive"))
      (node (ref "C47") (pin "2") (pinfunction "2_2") (pintype "passive"))
      (node (ref "C48") (pin "2") (pinfunction "2_2") (pintype "passive"))
      (node (ref "C49") (pin "2") (pinfunction "2_2") (pintype "passive"))
      (node (ref "C5") (pin "C") (pinfunction "-_C") (pintype "passive"))
      (node (ref "C50") (pin "2") (pinfunction "2_2") (pintype "passive"))
      (node (ref "C51") (pin "2") (pinfunction "2_2") (pintype "passive"))
      (node (ref "C52") (pin "2") (pinfunction "2_2") (pintype "passive"))
      (node (ref "C6") (pin "2") (pinfunction "2_2") (pintype "passive"))
      (node (ref "C7") (pin "2") (pinfunction "2_2") (pintype "passive"))
      (node (ref "C8") (pin "2") (pinfunction "2_2") (pintype "passive"))
      (node (ref "C9") (pin "2") (pinfunction "2_2") (pintype "passive"))
      (node (ref "D1") (pin "A") (pinfunction "A_A") (pintype "passive"))
      (node (ref "D4") (pin "A") (pinfunction "A_A") (pintype "passive"))
      (node (ref "DC1") (pin "1") (pinfunction "-VIN_1") (pintype "passive"))
      (node (ref "IC1") (pin "1") (pinfunction "ADJ_1") (pintype "input"))
      (node (ref "IC2") (pin "3") (pinfunction "GND_3") (pintype "power_in"))
      (node (ref "IC2") (pin "5") (pinfunction "~{ON}/OFF_5") (pintype "input"))
      (node (ref "IC3") (pin "1") (pinfunction "ADJ_1") (pintype "input"))
      (node (ref "IC5") (pin "2") (pinfunction "GND_2") (pintype "power_in"))
      (node (ref "J2") (pin "G-") (pinfunction "G-_G-") (pintype "bidirectional"))
      (node (ref "J2") (pin "GND") (pinfunction "GND_GND") (pintype "bidirectional"))
      (node (ref "J2") (pin "SHIELD0") (pinfunction "SHIELD0_SHIELD0") (pintype "bidirectional"))
      (node (ref "J2") (pin "SHIELD1") (pinfunction "SHIELD1_SHIELD1") (pintype "bidirectional"))
      (node (ref "J2") (pin "Y-") (pinfunction "Y-_Y-") (pintype "bidirectional"))
      (node (ref "J4") (pin "G-") (pinfunction "G-_G-") (pintype "bidirectional"))
      (node (ref "J4") (pin "GND") (pinfunction "GND_GND") (pintype "bidirectional"))
      (node (ref "J4") (pin "SHIELD0") (pinfunction "SHIELD0_SHIELD0") (pintype "bidirectional"))
      (node (ref "J4") (pin "SHIELD1") (pinfunction "SHIELD1_SHIELD1") (pintype "bidirectional"))
      (node (ref "J4") (pin "Y-") (pinfunction "Y-_Y-") (pintype "bidirectional"))
      (node (ref "JP1") (pin "1") (pinfunction "1_1") (pintype "passive"))
      (node (ref "JP12") (pin "7") (pinfunction "7_7") (pintype "passive"))
      (node (ref "JP2") (pin "1") (pinfunction "1_1") (pintype "passive"))
      (node (ref "JP24") (pin "3") (pinfunction "3_3") (pintype "passive"))
      (node (ref "JP25") (pin "1") (pinfunction "1_1") (pintype "passive"))
      (node (ref "JP3") (pin "GND") (pinfunction "GND_GND") (pintype "bidirectional"))
      (node (ref "JP4") (pin "1") (pinfunction "1_1") (pintype "passive"))
      (node (ref "JP5") (pin "2") (pinfunction "2_2") (pintype "passive"))
      (node (ref "JP6") (pin "2") (pinfunction "2_2") (pintype "passive"))
      (node (ref "JP7") (pin "1") (pinfunction "1_1") (pintype "passive"))
      (node (ref "LED10") (pin "C") (pinfunction "C_C") (pintype "passive"))
      (node (ref "LED11") (pin "C") (pinfunction "C_C") (pintype "passive"))
      (node (ref "LED12") (pin "C") (pinfunction "C_C") (pintype "passive"))
      (node (ref "LED13") (pin "C") (pinfunction "C_C") (pintype "passive"))
      (node (ref "LED9") (pin "C") (pinfunction "C_C") (pintype "passive"))
      (node (ref "OK1") (pin "3") (pinfunction "EMIT_3") (pintype "passive"))
      (node (ref "OK2") (pin "3") (pinfunction "EMIT_3") (pintype "passive"))
      (node (ref "OK3") (pin "3") (pinfunction "EMIT_3") (pintype "passive"))
      (node (ref "OK4") (pin "3") (pinfunction "EMIT_3") (pintype "passive"))
      (node (ref "OK5") (pin "3") (pinfunction "EMIT_3") (pintype "passive"))
      (node (ref "OK6") (pin "3") (pinfunction "EMIT_3") (pintype "passive"))
      (node (ref "OK7") (pin "3") (pinfunction "EMIT_3") (pintype "passive"))
      (node (ref "OK8") (pin "3") (pinfunction "EMIT_3") (pintype "passive"))
      (node (ref "R1") (pin "1") (pinfunction "1_1") (pintype "passive"))
      (node (ref "R10") (pin "1") (pinfunction "1_1") (pintype "passive"))
      (node (ref "R19") (pin "1") (pinfunction "1_1") (pintype "passive"))
      (node (ref "R30") (pin "3") (pinfunction "CW_3") (pintype "passive"))
      (node (ref "R47") (pin "1") (pinfunction "1_1") (pintype "passive"))
      (node (ref "R48") (pin "2") (pinfunction "2_2") (pintype "passive"))
      (node (ref "R57") (pin "1") (pinfunction "1_1") (pintype "passive"))
      (node (ref "R9") (pin "2") (pinfunction "2_2") (pintype "passive"))
      (node (ref "S1") (pin "3") (pinfunction "3_3") (pintype "passive"))
      (node (ref "S1") (pin "4") (pinfunction "4_4") (pintype "passive"))
      (node (ref "S2") (pin "3") (pinfunction "3_3") (pintype "passive"))
      (node (ref "S2") (pin "4") (pinfunction "4_4") (pintype "passive"))
      (node (ref "S5") (pin "3") (pinfunction "3_3") (pintype "passive"))
      (node (ref "S5") (pin "4") (pinfunction "4_4") (pintype "passive"))
      (node (ref "T1") (pin "2") (pinfunction "S_2") (pintype "passive"))
      (node (ref "T2") (pin "2") (pinfunction "S_2") (pintype "passive"))
      (node (ref "T3") (pin "2") (pinfunction "S_2") (pintype "passive"))
      (node (ref "T4") (pin "2") (pinfunction "S_2") (pintype "passive"))
      (node (ref "U$1") (pin "1") (pinfunction "VSSOSC_1") (pintype "bidirectional"))
      (node (ref "U$1") (pin "13") (pinfunction "VSSPLL_13") (pintype "bidirectional"))
      (node (ref "U$1") (pin "14") (pinfunction "VSSRX_14") (pintype "bidirectional"))
      (node (ref "U$1") (pin "19") (pinfunction "VSSTX1_19") (pintype "bidirectional"))
      (node (ref "U$1") (pin "22") (pinfunction "VSSTX2_22") (pintype "bidirectional"))
      (node (ref "U$1") (pin "33") (pinfunction "VSS1_33") (pintype "bidirectional"))
      (node (ref "U$1") (pin "42") (pinfunction "VSS2_42") (pintype "bidirectional"))
      (node (ref "U$2") (pin "P$2") (pinfunction "P$2_P$2") (pintype "bidirectional"))
      (node (ref "U$3") (pin "1") (pinfunction "VSSOSC_1") (pintype "bidirectional"))
      (node (ref "U$3") (pin "13") (pinfunction "VSSPLL_13") (pintype "bidirectional"))
      (node (ref "U$3") (pin "14") (pinfunction "VSSRX_14") (pintype "bidirectional"))
      (node (ref "U$3") (pin "19") (pinfunction "VSSTX1_19") (pintype "bidirectional"))
      (node (ref "U$3") (pin "22") (pinfunction "VSSTX2_22") (pintype "bidirectional"))
      (node (ref "U$3") (pin "33") (pinfunction "VSS1_33") (pintype "bidirectional"))
      (node (ref "U$3") (pin "42") (pinfunction "VSS2_42") (pintype "bidirectional"))
      (node (ref "U$4") (pin "P$4") (pinfunction "GND_P$4") (pintype "bidirectional"))
      (node (ref "U$5") (pin "16") (pinfunction "VSS_16") (pintype "bidirectional"))
      (node (ref "U$5") (pin "32") (pinfunction "VSS_32") (pintype "bidirectional"))
      (node (ref "U1") (pin "5") (pinfunction "GND_5") (pintype "bidirectional"))
      (node (ref "U2") (pin "23") (pinfunction "VSS_1_23") (pintype "bidirectional"))
      (node (ref "U2") (pin "35") (pinfunction "VSS_2_35") (pintype "passive"))
      (node (ref "U2") (pin "47") (pinfunction "VSS_3_47") (pintype "passive"))
      (node (ref "U2") (pin "8") (pinfunction "VSSA_8") (pintype "passive"))
      (node (ref "U3") (pin "4") (pinfunction "GND_4") (pintype "bidirectional"))
      (node (ref "U4") (pin "15") (pinfunction "GND_15") (pintype "passive"))
      (node (ref "U5") (pin "4") (pinfunction "GND_4") (pintype "passive"))
      (node (ref "U6") (pin "1") (pinfunction "VSS_1") (pintype "power_in"))
      (node (ref "U6") (pin "10") (pinfunction "DB3_10") (pintype "bidirectional"))
      (node (ref "U6") (pin "16") (pinfunction "K_16") (pintype "power_in"))
      (node (ref "U6") (pin "5") (pinfunction "R/W_5") (pintype "input"))
      (node (ref "U6") (pin "7") (pinfunction "DB0_7") (pintype "bidirectional"))
      (node (ref "U6") (pin "8") (pinfunction "DB1_8") (pintype "bidirectional"))
      (node (ref "U6") (pin "9") (pinfunction "DB2_9") (pintype "bidirectional"))
      (node (ref "X1") (pin "5") (pinfunction "5_5") (pintype "passive"))
    )
    (net (code "25") (name "G_RESET") (class "Default")
      (node (ref "C10") (pin "1") (pinfunction "1_1") (pintype "passive"))
      (node (ref "R4") (pin "1") (pinfunction "1_1") (pintype "passive"))
      (node (ref "S5") (pin "1") (pinfunction "1_1") (pintype "passive"))
      (node (ref "S5") (pin "2") (pinfunction "2_2") (pintype "passive"))
      (node (ref "U$5") (pin "4") (pinfunction "NRST_4") (pintype "bidirectional"))
      (node (ref "U2") (pin "7") (pinfunction "NRST_7") (pintype "bidirectional"))
    )
    (net (code "26") (name "I2C1_SCL") (class "Default")
      (node (ref "IC5") (pin "6") (pinfunction "SCL_6") (pintype "input"))
      (node (ref "JP4") (pin "2") (pinfunction "2_2") (pintype "passive"))
      (node (ref "R29") (pin "2") (pinfunction "2_2") (pintype "passive"))
      (node (ref "U2") (pin "42") (pinfunction "PB6_42") (pintype "bidirectional"))
    )
    (net (code "27") (name "I2C1_SDA") (class "Default")
      (node (ref "IC5") (pin "1") (pinfunction "SDA_1") (pintype "bidirectional"))
      (node (ref "JP4") (pin "3") (pinfunction "3_3") (pintype "passive"))
      (node (ref "R28") (pin "2") (pinfunction "2_2") (pintype "passive"))
      (node (ref "U2") (pin "43") (pinfunction "PB7_43") (pintype "bidirectional"))
    )
    (net (code "28") (name "LA1") (class "Default")
      (node (ref "J4") (pin "G+") (pinfunction "G+_G+") (pintype "bidirectional"))
      (node (ref "R17") (pin "1") (pinfunction "1_1") (pintype "passive"))
    )
    (net (code "29") (name "LA2") (class "Default")
      (node (ref "J2") (pin "G+") (pinfunction "G+_G+") (pintype "bidirectional"))
      (node (ref "R26") (pin "1") (pinfunction "1_1") (pintype "passive"))
    )
    (net (code "30") (name "LB1") (class "Default")
      (node (ref "J4") (pin "Y+") (pinfunction "Y+_Y+") (pintype "bidirectional"))
      (node (ref "R18") (pin "1") (pinfunction "1_1") (pintype "passive"))
    )
    (net (code "31") (name "LB2") (class "Default")
      (node (ref "J2") (pin "Y+") (pinfunction "Y+_Y+") (pintype "bidirectional"))
      (node (ref "R27") (pin "1") (pinfunction "1_1") (pintype "passive"))
    )
    (net (code "32") (name "LCD_D4") (class "Default")
      (node (ref "U$5") (pin "27") (pinfunction "PB4_27") (pintype "bidirectional"))
      (node (ref "U6") (pin "11") (pinfunction "DB4_11") (pintype "bidirectional"))
    )
    (net (code "33") (name "LCD_D5") (class "Default")
      (node (ref "U$5") (pin "28") (pinfunction "PB5_28") (pintype "bidirectional"))
      (node (ref "U6") (pin "12") (pinfunction "DB5_12") (pintype "bidirectional"))
    )
    (net (code "34") (name "LCD_D6") (class "Default")
      (node (ref "U$5") (pin "29") (pinfunction "PB6_29") (pintype "bidirectional"))
      (node (ref "U6") (pin "13") (pinfunction "DB6_13") (pintype "bidirectional"))
    )
    (net (code "35") (name "LCD_D7") (class "Default")
      (node (ref "U$5") (pin "30") (pinfunction "PB7_30") (pintype "bidirectional"))
      (node (ref "U6") (pin "14") (pinfunction "DB7_14") (pintype "bidirectional"))
    )
    (net (code "36") (name "LCD_E") (class "Default")
      (node (ref "U$5") (pin "26") (pinfunction "PB3_26") (pintype "bidirectional"))
      (node (ref "U6") (pin "6") (pinfunction "E_6") (pintype "input"))
    )
    (net (code "37") (name "LCD_RS") (class "Default")
      (node (ref "U$5") (pin "25") (pinfunction "PA15_25") (pintype "bidirectional"))
      (node (ref "U6") (pin "4") (pinfunction "RS_4") (pintype "input"))
    )
    (net (code "38") (name "Net-(BAT1-+)") (class "Default")
      (node (ref "BAT1") (pin "1") (pinfunction "+_1") (pintype "power_in"))
      (node (ref "D5") (pin "2") (pinfunction "A2_2") (pintype "passive"))
    )
    (net (code "39") (name "Net-(C26-+)") (class "Default")
      (node (ref "C26") (pin "A") (pinfunction "+_A") (pintype "passive"))
      (node (ref "U$1") (pin "43") (pinfunction "VCAP_43") (pintype "bidirectional"))
    )
    (net (code "40") (name "Net-(C40-+)") (class "Default")
      (node (ref "C40") (pin "A") (pinfunction "+_A") (pintype "passive"))
      (node (ref "U$3") (pin "43") (pinfunction "VCAP_43") (pintype "bidirectional"))
    )
    (net (code "41") (name "Net-(D8-PadA)") (class "Default")
      (node (ref "D8") (pin "A") (pinfunction "A_A") (pintype "passive"))
      (node (ref "U$2") (pin "P$1") (pinfunction "P$1_P$1") (pintype "bidirectional"))
    )
    (net (code "42") (name "Net-(DC1-+VIN)") (class "Default")
      (node (ref "DC1") (pin "2") (pinfunction "+VIN_2") (pintype "passive"))
      (node (ref "IC3") (pin "4") (pinfunction "OUT_4") (pintype "passive"))
    )
    (net (code "43") (name "Net-(DC1-+VOUT)") (class "Default")
      (node (ref "DC1") (pin "4") (pinfunction "+VOUT_4") (pintype "passive"))
      (node (ref "L2") (pin "1") (pinfunction "1_1") (pintype "passive"))
    )
    (net (code "44") (name "Net-(IC1-IN)") (class "Default")
      (node (ref "C52") (pin "1") (pinfunction "1_1") (pintype "passive"))
      (node (ref "IC1") (pin "3") (pinfunction "IN_3") (pintype "input"))
      (node (ref "JP9") (pin "2") (pinfunction "2_2") (pintype "passive"))
      (node (ref "R60") (pin "2") (pinfunction "2_2") (pintype "passive"))
    )
    (net (code "45") (name "Net-(IC2-FB)") (class "Default")
      (node (ref "IC2") (pin "4") (pinfunction "FB_4") (pintype "input"))
      (node (ref "R1") (pin "2") (pinfunction "2_2") (pintype "passive"))
      (node (ref "R2") (pin "2") (pinfunction "2_2") (pintype "passive"))
    )
    (net (code "46") (name "Net-(IC2-OUT)") (class "Default")
      (node (ref "D1") (pin "C") (pinfunction "C_C") (pintype "passive"))
      (node (ref "IC2") (pin "2") (pinfunction "OUT_2") (pintype "output"))
      (node (ref "L1") (pin "P$1") (pinfunction "1_P$1") (pintype "passive"))
    )
    (net (code "47") (name "Net-(IC2-VIN)") (class "Default")
      (node (ref "C51") (pin "1") (pinfunction "1_1") (pintype "passive"))
      (node (ref "IC2") (pin "1") (pinfunction "VIN_1") (pintype "input"))
      (node (ref "JP8") (pin "2") (pinfunction "2_2") (pintype "passive"))
      (node (ref "R59") (pin "2") (pinfunction "2_2") (pintype "passive"))
    )
    (net (code "48") (name "Net-(JP3-PadD+)") (class "Default")
      (node (ref "JP3") (pin "D+") (pinfunction "D+_D+") (pintype "bidirectional"))
      (node (ref "R6") (pin "2") (pinfunction "2_2") (pintype "passive"))
    )
    (net (code "49") (name "Net-(JP3-PadD-)") (class "Default")
      (node (ref "JP3") (pin "D-") (pinfunction "D-_D-") (pintype "bidirectional"))
      (node (ref "R5") (pin "2") (pinfunction "2_2") (pintype "passive"))
    )
    (net (code "50") (name "Net-(JP20-Pad1)") (class "Default")
      (node (ref "JP20") (pin "1") (pinfunction "1_1") (pintype "passive"))
      (node (ref "K1") (pin "O") (pinfunction "O_O") (pintype "passive"))
    )
    (net (code "51") (name "Net-(JP20-Pad2)") (class "Default")
      (node (ref "JP20") (pin "2") (pinfunction "2_2") (pintype "passive"))
      (node (ref "K1") (pin "P") (pinfunction "P_P") (pintype "passive"))
    )
    (net (code "52") (name "Net-(JP20-Pad3)") (class "Default")
      (node (ref "JP20") (pin "3") (pinfunction "3_3") (pintype "passive"))
      (node (ref "K1") (pin "S") (pinfunction "S_S") (pintype "passive"))
    )
    (net (code "53") (name "Net-(JP21-Pad1)") (class "Default")
      (node (ref "JP21") (pin "1") (pinfunction "1_1") (pintype "passive"))
      (node (ref "K2") (pin "O") (pinfunction "O_O") (pintype "passive"))
    )
    (net (code "54") (name "Net-(JP21-Pad2)") (class "Default")
      (node (ref "JP21") (pin "2") (pinfunction "2_2") (pintype "passive"))
      (node (ref "K2") (pin "P") (pinfunction "P_P") (pintype "passive"))
    )
    (net (code "55") (name "Net-(JP21-Pad3)") (class "Default")
      (node (ref "JP21") (pin "3") (pinfunction "3_3") (pintype "passive"))
      (node (ref "K2") (pin "S") (pinfunction "S_S") (pintype "passive"))
    )
    (net (code "56") (name "Net-(JP22-Pad1)") (class "Default")
      (node (ref "JP22") (pin "1") (pinfunction "1_1") (pintype "passive"))
      (node (ref "K3") (pin "O") (pinfunction "O_O") (pintype "passive"))
    )
    (net (code "57") (name "Net-(JP22-Pad2)") (class "Default")
      (node (ref "JP22") (pin "2") (pinfunction "2_2") (pintype "passive"))
      (node (ref "K3") (pin "P") (pinfunction "P_P") (pintype "passive"))
    )
    (net (code "58") (name "Net-(JP22-Pad3)") (class "Default")
      (node (ref "JP22") (pin "3") (pinfunction "3_3") (pintype "passive"))
      (node (ref "K3") (pin "S") (pinfunction "S_S") (pintype "passive"))
    )
    (net (code "59") (name "Net-(JP23-Pad1)") (class "Default")
      (node (ref "JP23") (pin "1") (pinfunction "1_1") (pintype "passive"))
      (node (ref "K4") (pin "O") (pinfunction "O_O") (pintype "passive"))
    )
    (net (code "60") (name "Net-(JP23-Pad2)") (class "Default")
      (node (ref "JP23") (pin "2") (pinfunction "2_2") (pintype "passive"))
      (node (ref "K4") (pin "P") (pinfunction "P_P") (pintype "passive"))
    )
    (net (code "61") (name "Net-(JP23-Pad3)") (class "Default")
      (node (ref "JP23") (pin "3") (pinfunction "3_3") (pintype "passive"))
      (node (ref "K4") (pin "S") (pinfunction "S_S") (pintype "passive"))
    )
    (net (code "62") (name "Net-(L3-1)") (class "Default")
      (node (ref "D4") (pin "C") (pinfunction "C_C") (pintype "passive"))
      (node (ref "L3") (pin "P$1") (pinfunction "1_P$1") (pintype "passive"))
      (node (ref "U3") (pin "2") (pinfunction "SWE_2") (pintype "bidirectional"))
    )
    (net (code "63") (name "Net-(L4-Pad1)") (class "Default")
      (node (ref "L4") (pin "1") (pinfunction "1_1") (pintype "passive"))
      (node (ref "R12") (pin "2") (pinfunction "2_2") (pintype "passive"))
      (node (ref "R13") (pin "2") (pinfunction "2_2") (pintype "passive"))
      (node (ref "R16") (pin "2") (pinfunction "2_2") (pintype "passive"))
    )
    (net (code "64") (name "Net-(L5-Pad1)") (class "Default")
      (node (ref "L5") (pin "1") (pinfunction "1_1") (pintype "passive"))
      (node (ref "R21") (pin "2") (pinfunction "2_2") (pintype "passive"))
      (node (ref "R22") (pin "2") (pinfunction "2_2") (pintype "passive"))
      (node (ref "R25") (pin "2") (pinfunction "2_2") (pintype "passive"))
    )
    (net (code "65") (name "Net-(LED1-PadC)") (class "Default")
      (node (ref "LED1") (pin "C") (pinfunction "C_C") (pintype "passive"))
      (node (ref "R31") (pin "2") (pinfunction "2_2") (pintype "passive"))
    )
    (net (code "66") (name "Net-(LED2-PadC)") (class "Default")
      (node (ref "LED2") (pin "C") (pinfunction "C_C") (pintype "passive"))
      (node (ref "R32") (pin "2") (pinfunction "2_2") (pintype "passive"))
    )
    (net (code "67") (name "Net-(LED3-PadC)") (class "Default")
      (node (ref "LED3") (pin "C") (pinfunction "C_C") (pintype "passive"))
      (node (ref "R34") (pin "2") (pinfunction "2_2") (pintype "passive"))
    )
    (net (code "68") (name "Net-(LED4-PadC)") (class "Default")
      (node (ref "LED4") (pin "C") (pinfunction "C_C") (pintype "passive"))
      (node (ref "R36") (pin "2") (pinfunction "2_2") (pintype "passive"))
    )
    (net (code "69") (name "Net-(LED5-PadC)") (class "Default")
      (node (ref "LED5") (pin "C") (pinfunction "C_C") (pintype "passive"))
      (node (ref "R38") (pin "2") (pinfunction "2_2") (pintype "passive"))
    )
    (net (code "70") (name "Net-(LED6-PadC)") (class "Default")
      (node (ref "LED6") (pin "C") (pinfunction "C_C") (pintype "passive"))
      (node (ref "R50") (pin "2") (pinfunction "2_2") (pintype "passive"))
    )
    (net (code "71") (name "Net-(LED7-PadC)") (class "Default")
      (node (ref "LED7") (pin "C") (pinfunction "C_C") (pintype "passive"))
      (node (ref "R52") (pin "2") (pinfunction "2_2") (pintype "passive"))
    )
    (net (code "72") (name "Net-(LED8-PadC)") (class "Default")
      (node (ref "LED8") (pin "C") (pinfunction "C_C") (pintype "passive"))
      (node (ref "R54") (pin "2") (pinfunction "2_2") (pintype "passive"))
    )
    (net (code "73") (name "Net-(LED9-PadA)") (class "Default")
      (node (ref "LED9") (pin "A") (pinfunction "A_A") (pintype "passive"))
      (node (ref "R39") (pin "2") (pinfunction "2_2") (pintype "passive"))
    )
    (net (code "74") (name "Net-(LED10-PadA)") (class "Default")
      (node (ref "LED10") (pin "A") (pinfunction "A_A") (pintype "passive"))
      (node (ref "R40") (pin "2") (pinfunction "2_2") (pintype "passive"))
    )
    (net (code "75") (name "Net-(LED11-PadA)") (class "Default")
      (node (ref "LED11") (pin "A") (pinfunction "A_A") (pintype "passive"))
      (node (ref "R41") (pin "2") (pinfunction "2_2") (pintype "passive"))
    )
    (net (code "76") (name "Net-(LED12-PadA)") (class "Default")
      (node (ref "LED12") (pin "A") (pinfunction "A_A") (pintype "passive"))
      (node (ref "R42") (pin "2") (pinfunction "2_2") (pintype "passive"))
    )
    (net (code "77") (name "Net-(LED13-PadA)") (class "Default")
      (node (ref "LED13") (pin "A") (pinfunction "A_A") (pintype "passive"))
      (node (ref "R44") (pin "2") (pinfunction "2_2") (pintype "passive"))
    )
    (net (code "78") (name "Net-(OK1-A)") (class "Default")
      (node (ref "OK1") (pin "1") (pinfunction "A_1") (pintype "passive"))
      (node (ref "R3") (pin "2") (pinfunction "2_2") (pintype "passive"))
    )
    (net (code "79") (name "Net-(OK1-C)") (class "Default")
      (node (ref "JP13") (pin "1") (pinfunction "1_1") (pintype "passive"))
      (node (ref "OK1") (pin "2") (pinfunction "C_2") (pintype "passive"))
    )
    (net (code "80") (name "Net-(OK2-A)") (class "Default")
      (node (ref "OK2") (pin "1") (pinfunction "A_1") (pintype "passive"))
      (node (ref "R33") (pin "2") (pinfunction "2_2") (pintype "passive"))
    )
    (net (code "81") (name "Net-(OK2-C)") (class "Default")
      (node (ref "JP14") (pin "1") (pinfunction "1_1") (pintype "passive"))
      (node (ref "OK2") (pin "2") (pinfunction "C_2") (pintype "passive"))
    )
    (net (code "82") (name "Net-(OK3-A)") (class "Default")
      (node (ref "OK3") (pin "1") (pinfunction "A_1") (pintype "passive"))
      (node (ref "R35") (pin "2") (pinfunction "2_2") (pintype "passive"))
    )
    (net (code "83") (name "Net-(OK3-C)") (class "Default")
      (node (ref "JP15") (pin "1") (pinfunction "1_1") (pintype "passive"))
      (node (ref "OK3") (pin "2") (pinfunction "C_2") (pintype "passive"))
    )
    (net (code "84") (name "Net-(OK4-A)") (class "Default")
      (node (ref "OK4") (pin "1") (pinfunction "A_1") (pintype "passive"))
      (node (ref "R37") (pin "2") (pinfunction "2_2") (pintype "passive"))
    )
    (net (code "85") (name "Net-(OK4-C)") (class "Default")
      (node (ref "JP18") (pin "1") (pinfunction "1_1") (pintype "passive"))
      (node (ref "OK4") (pin "2") (pinfunction "C_2") (pintype "passive"))
    )
    (net (code "86") (name "Net-(OK5-A)") (class "Default")
      (node (ref "OK5") (pin "1") (pinfunction "A_1") (pintype "passive"))
      (node (ref "R49") (pin "2") (pinfunction "2_2") (pintype "passive"))
    )
    (net (code "87") (name "Net-(OK5-C)") (class "Default")
      (node (ref "JP10") (pin "1") (pinfunction "1_1") (pintype "passive"))
      (node (ref "OK5") (pin "2") (pinfunction "C_2") (pintype "passive"))
    )
    (net (code "88") (name "Net-(OK6-A)") (class "Default")
      (node (ref "OK6") (pin "1") (pinfunction "A_1") (pintype "passive"))
      (node (ref "R51") (pin "2") (pinfunction "2_2") (pintype "passive"))
    )
    (net (code "89") (name "Net-(OK6-C)") (class "Default")
      (node (ref "JP19") (pin "1") (pinfunction "1_1") (pintype "passive"))
      (node (ref "OK6") (pin "2") (pinfunction "C_2") (pintype "passive"))
    )
    (net (code "90") (name "Net-(OK7-A)") (class "Default")
      (node (ref "OK7") (pin "1") (pinfunction "A_1") (pintype "passive"))
      (node (ref "R53") (pin "2") (pinfunction "2_2") (pintype "passive"))
    )
    (net (code "91") (name "Net-(OK7-C)") (class "Default")
      (node (ref "JP16") (pin "1") (pinfunction "1_1") (pintype "passive"))
      (node (ref "OK7") (pin "2") (pinfunction "C_2") (pintype "passive"))
    )
    (net (code "92") (name "Net-(OK8-A)") (class "Default")
      (node (ref "OK8") (pin "1") (pinfunction "A_1") (pintype "passive"))
      (node (ref "R55") (pin "2") (pinfunction "2_2") (pintype "passive"))
    )
    (net (code "93") (name "Net-(OK8-C)") (class "Default")
      (node (ref "JP17") (pin "1") (pinfunction "1_1") (pintype "passive"))
      (node (ref "OK8") (pin "2") (pinfunction "C_2") (pintype "passive"))
    )
    (net (code "94") (name "Net-(R30-WIPER)") (class "Default")
      (node (ref "R30") (pin "2") (pinfunction "WIPER_2") (pintype "passive"))
      (node (ref "U6") (pin "3") (pinfunction "VO_3") (pintype "bidirectional"))
    )
    (net (code "95") (name "Net-(T1-D)") (class "Default")
      (node (ref "D7") (pin "A") (pinfunction "A_A") (pintype "passive"))
      (node (ref "K1") (pin "2") (pinfunction "2_2") (pintype "passive"))
      (node (ref "T1") (pin "3") (pinfunction "D_3") (pintype "passive"))
    )
    (net (code "96") (name "Net-(T2-D)") (class "Default")
      (node (ref "D6") (pin "A") (pinfunction "A_A") (pintype "passive"))
      (node (ref "K2") (pin "2") (pinfunction "2_2") (pintype "passive"))
      (node (ref "T2") (pin "3") (pinfunction "D_3") (pintype "passive"))
    )
    (net (code "97") (name "Net-(T3-D)") (class "Default")
      (node (ref "D2") (pin "A") (pinfunction "A_A") (pintype "passive"))
      (node (ref "K3") (pin "2") (pinfunction "2_2") (pintype "passive"))
      (node (ref "T3") (pin "3") (pinfunction "D_3") (pintype "passive"))
    )
    (net (code "98") (name "Net-(T4-D)") (class "Default")
      (node (ref "D3") (pin "A") (pinfunction "A_A") (pintype "passive"))
      (node (ref "K4") (pin "2") (pinfunction "2_2") (pintype "passive"))
      (node (ref "T4") (pin "3") (pinfunction "D_3") (pintype "passive"))
    )
    (net (code "99") (name "Net-(U$1-LEDA)") (class "Default")
      (node (ref "R17") (pin "2") (pinfunction "2_2") (pintype "passive"))
      (node (ref "U$1") (pin "10") (pinfunction "LEDA_10") (pintype "bidirectional"))
    )
    (net (code "100") (name "Net-(U$1-LEDB)") (class "Default")
      (node (ref "R18") (pin "2") (pinfunction "2_2") (pintype "passive"))
      (node (ref "U$1") (pin "9") (pinfunction "LEDB_9") (pintype "bidirectional"))
    )
    (net (code "101") (name "Net-(U$1-OSC1)") (class "Default")
      (node (ref "C24") (pin "1") (pinfunction "1_1") (pintype "passive"))
      (node (ref "U$1") (pin "3") (pinfunction "OSC1_3") (pintype "bidirectional"))
      (node (ref "Y3") (pin "P$1") (pinfunction "1_P$1") (pintype "passive"))
    )
    (net (code "102") (name "Net-(U$1-OSC2)") (class "Default")
      (node (ref "C25") (pin "1") (pinfunction "1_1") (pintype "passive"))
      (node (ref "U$1") (pin "2") (pinfunction "OSC2_2") (pintype "bidirectional"))
      (node (ref "Y3") (pin "P$2") (pinfunction "2_P$2") (pintype "passive"))
    )
    (net (code "103") (name "Net-(U$1-RBIAS)") (class "Default")
      (node (ref "R10") (pin "2") (pinfunction "2_2") (pintype "passive"))
      (node (ref "U$1") (pin "11") (pinfunction "RBIAS_11") (pintype "bidirectional"))
    )
    (net (code "104") (name "Net-(U$1-TPIN+)") (class "Default")
      (node (ref "C30") (pin "1") (pinfunction "1_1") (pintype "passive"))
      (node (ref "R15") (pin "2") (pinfunction "2_2") (pintype "passive"))
      (node (ref "U$1") (pin "16") (pinfunction "TPIN+_16") (pintype "bidirectional"))
    )
    (net (code "105") (name "Net-(U$1-TPIN-)") (class "Default")
      (node (ref "C31") (pin "1") (pinfunction "1_1") (pintype "passive"))
      (node (ref "R14") (pin "2") (pinfunction "2_2") (pintype "passive"))
      (node (ref "U$1") (pin "17") (pinfunction "TPIN-_17") (pintype "bidirectional"))
    )
    (net (code "106") (name "Net-(U$3-LEDA)") (class "Default")
      (node (ref "R26") (pin "2") (pinfunction "2_2") (pintype "passive"))
      (node (ref "U$3") (pin "10") (pinfunction "LEDA_10") (pintype "bidirectional"))
    )
    (net (code "107") (name "Net-(U$3-LEDB)") (class "Default")
      (node (ref "R27") (pin "2") (pinfunction "2_2") (pintype "passive"))
      (node (ref "U$3") (pin "9") (pinfunction "LEDB_9") (pintype "bidirectional"))
    )
    (net (code "108") (name "Net-(U$3-OSC1)") (class "Default")
      (node (ref "C36") (pin "1") (pinfunction "1_1") (pintype "passive"))
      (node (ref "U$3") (pin "3") (pinfunction "OSC1_3") (pintype "bidirectional"))
      (node (ref "Y4") (pin "P$1") (pinfunction "1_P$1") (pintype "passive"))
    )
    (net (code "109") (name "Net-(U$3-OSC2)") (class "Default")
      (node (ref "C37") (pin "1") (pinfunction "1_1") (pintype "passive"))
      (node (ref "U$3") (pin "2") (pinfunction "OSC2_2") (pintype "bidirectional"))
      (node (ref "Y4") (pin "P$2") (pinfunction "2_P$2") (pintype "passive"))
    )
    (net (code "110") (name "Net-(U$3-RBIAS)") (class "Default")
      (node (ref "R19") (pin "2") (pinfunction "2_2") (pintype "passive"))
      (node (ref "U$3") (pin "11") (pinfunction "RBIAS_11") (pintype "bidirectional"))
    )
    (net (code "111") (name "Net-(U$3-TPIN+)") (class "Default")
      (node (ref "C42") (pin "1") (pinfunction "1_1") (pintype "passive"))
      (node (ref "R24") (pin "2") (pinfunction "2_2") (pintype "passive"))
      (node (ref "U$3") (pin "16") (pinfunction "TPIN+_16") (pintype "bidirectional"))
    )
    (net (code "112") (name "Net-(U$3-TPIN-)") (class "Default")
      (node (ref "C43") (pin "1") (pinfunction "1_1") (pintype "passive"))
      (node (ref "R23") (pin "2") (pinfunction "2_2") (pintype "passive"))
      (node (ref "U$3") (pin "17") (pinfunction "TPIN-_17") (pintype "bidirectional"))
    )
    (net (code "113") (name "Net-(U$4-S)") (class "Default")
      (node (ref "JP12") (pin "8") (pinfunction "8_8") (pintype "passive"))
      (node (ref "R43") (pin "1") (pinfunction "1_1") (pintype "passive"))
      (node (ref "U$4") (pin "P$2") (pinfunction "S_P$2") (pintype "bidirectional"))
    )
    (net (code "114") (name "Net-(U$5-BOOT0)") (class "Default")
      (node (ref "R48") (pin "1") (pinfunction "1_1") (pintype "passive"))
      (node (ref "U$5") (pin "31") (pinfunction "BOOT0_31") (pintype "bidirectional"))
    )
    (net (code "115") (name "Net-(U$5-PA13{slash}SWDIO)") (class "Default")
      (node (ref "JP2") (pin "3") (pinfunction "3_3") (pintype "passive"))
      (node (ref "U$5") (pin "23") (pinfunction "PA13/SWDIO_23") (pintype "bidirectional"))
    )
    (net (code "116") (name "Net-(U$5-PA14{slash}SWCLK)") (class "Default")
      (node (ref "JP2") (pin "2") (pinfunction "2_2") (pintype "passive"))
      (node (ref "U$5") (pin "24") (pinfunction "PA14/SWCLK_24") (pintype "bidirectional"))
    )
    (net (code "117") (name "Net-(U1-A)") (class "Default")
      (node (ref "JP24") (pin "1") (pinfunction "1_1") (pintype "passive"))
      (node (ref "R57") (pin "2") (pinfunction "2_2") (pintype "passive"))
      (node (ref "R58") (pin "2") (pinfunction "2_2") (pintype "passive"))
      (node (ref "U1") (pin "6") (pinfunction "A_6") (pintype "bidirectional"))
    )
    (net (code "118") (name "Net-(U1-B)") (class "Default")
      (node (ref "JP24") (pin "2") (pinfunction "2_2") (pintype "passive"))
      (node (ref "R56") (pin "2") (pinfunction "2_2") (pintype "passive"))
      (node (ref "R58") (pin "1") (pinfunction "1_1") (pintype "passive"))
      (node (ref "U1") (pin "7") (pinfunction "B_7") (pintype "bidirectional"))
    )
    (net (code "119") (name "Net-(U2-BOOT0)") (class "Default")
      (node (ref "R47") (pin "2") (pinfunction "2_2") (pintype "passive"))
      (node (ref "U2") (pin "44") (pinfunction "BOOT0_44") (pintype "bidirectional"))
    )
    (net (code "120") (name "Net-(U2-PC14-OSC32_IN)") (class "Default")
      (node (ref "C12") (pin "1") (pinfunction "1_1") (pintype "passive"))
      (node (ref "U2") (pin "3") (pinfunction "PC14-OSC32_IN_3") (pintype "bidirectional"))
      (node (ref "Y1") (pin "1") (pinfunction "1_1") (pintype "passive"))
    )
    (net (code "121") (name "Net-(U2-PC15-OSC32_OUT)") (class "Default")
      (node (ref "C11") (pin "1") (pinfunction "1_1") (pintype "passive"))
      (node (ref "U2") (pin "4") (pinfunction "PC15-OSC32_OUT_4") (pintype "bidirectional"))
      (node (ref "Y1") (pin "4") (pinfunction "2_4") (pintype "passive"))
    )
    (net (code "122") (name "Net-(U2-PD0-OSC_IN)") (class "Default")
      (node (ref "C13") (pin "1") (pinfunction "1_1") (pintype "passive"))
      (node (ref "R46") (pin "2") (pinfunction "2_2") (pintype "passive"))
      (node (ref "U2") (pin "5") (pinfunction "PD0-OSC_IN_5") (pintype "bidirectional"))
      (node (ref "Y2") (pin "2") (pinfunction "2_2") (pintype "passive"))
    )
    (net (code "123") (name "Net-(U2-PD1-OSC_OUT)") (class "Default")
      (node (ref "C14") (pin "1") (pinfunction "1_1") (pintype "passive"))
      (node (ref "R46") (pin "1") (pinfunction "1_1") (pintype "passive"))
      (node (ref "U2") (pin "6") (pinfunction "PD1-OSC_OUT_6") (pintype "bidirectional"))
      (node (ref "Y2") (pin "1") (pinfunction "1_1") (pintype "passive"))
    )
    (net (code "124") (name "Net-(U3-COMP)") (class "Default")
      (node (ref "R8") (pin "1") (pinfunction "1_1") (pintype "passive"))
      (node (ref "R9") (pin "1") (pinfunction "1_1") (pintype "passive"))
      (node (ref "U3") (pin "5") (pinfunction "COMP_5") (pintype "bidirectional"))
    )
    (net (code "125") (name "Net-(U3-TC)") (class "Default")
      (node (ref "C17") (pin "1") (pinfunction "1_1") (pintype "passive"))
      (node (ref "U3") (pin "3") (pinfunction "TC_3") (pintype "bidirectional"))
    )
    (net (code "126") (name "Net-(U4-C1+)") (class "Default")
      (node (ref "C18") (pin "1") (pinfunction "1_1") (pintype "passive"))
      (node (ref "U4") (pin "1") (pinfunction "C1+_1") (pintype "input"))
    )
    (net (code "127") (name "Net-(U4-C1-)") (class "Default")
      (node (ref "C18") (pin "2") (pinfunction "2_2") (pintype "passive"))
      (node (ref "U4") (pin "3") (pinfunction "C1-_3") (pintype "input"))
    )
    (net (code "128") (name "Net-(U4-C2+)") (class "Default")
      (node (ref "C19") (pin "2") (pinfunction "2_2") (pintype "passive"))
      (node (ref "U4") (pin "4") (pinfunction "C2+_4") (pintype "input"))
    )
    (net (code "129") (name "Net-(U4-C2-)") (class "Default")
      (node (ref "C19") (pin "1") (pinfunction "1_1") (pintype "passive"))
      (node (ref "U4") (pin "5") (pinfunction "C2-_5") (pintype "input"))
    )
    (net (code "130") (name "Net-(U4-V+)") (class "Default")
      (node (ref "C21") (pin "2") (pinfunction "2_2") (pintype "passive"))
      (node (ref "U4") (pin "2") (pinfunction "V+_2") (pintype "input"))
    )
    (net (code "131") (name "Net-(U4-V-)") (class "Default")
      (node (ref "C20") (pin "2") (pinfunction "2_2") (pintype "passive"))
      (node (ref "U4") (pin "6") (pinfunction "V-_6") (pintype "input"))
    )
    (net (code "132") (name "RS485EN") (class "Default")
      (node (ref "U1") (pin "2") (pinfunction "~{RE}_2") (pintype "bidirectional"))
      (node (ref "U1") (pin "3") (pinfunction "DE_3") (pintype "bidirectional"))
      (node (ref "U2") (pin "38") (pinfunction "PA15_38") (pintype "bidirectional"))
    )
    (net (code "133") (name "RX1+") (class "Default")
      (node (ref "C30") (pin "2") (pinfunction "2_2") (pintype "passive"))
      (node (ref "J4") (pin "RD+") (pinfunction "RD+_RD+") (pintype "bidirectional"))
    )
    (net (code "134") (name "RX1-") (class "Default")
      (node (ref "C31") (pin "2") (pinfunction "2_2") (pintype "passive"))
      (node (ref "J4") (pin "RD-") (pinfunction "RD-_RD-") (pintype "bidirectional"))
    )
    (net (code "135") (name "RX1_CT") (class "Default")
      (node (ref "C32") (pin "2") (pinfunction "2_2") (pintype "passive"))
      (node (ref "J4") (pin "P5") (pinfunction "P5_P5") (pintype "bidirectional"))
      (node (ref "R14") (pin "1") (pinfunction "1_1") (pintype "passive"))
      (node (ref "R15") (pin "1") (pinfunction "1_1") (pintype "passive"))
    )
    (net (code "136") (name "RX2+") (class "Default")
      (node (ref "C42") (pin "2") (pinfunction "2_2") (pintype "passive"))
      (node (ref "J2") (pin "RD+") (pinfunction "RD+_RD+") (pintype "bidirectional"))
    )
    (net (code "137") (name "RX2-") (class "Default")
      (node (ref "C43") (pin "2") (pinfunction "2_2") (pintype "passive"))
      (node (ref "J2") (pin "RD-") (pinfunction "RD-_RD-") (pintype "bidirectional"))
    )
    (net (code "138") (name "RX2_CT") (class "Default")
      (node (ref "C44") (pin "2") (pinfunction "2_2") (pintype "passive"))
      (node (ref "J2") (pin "P5") (pinfunction "P5_P5") (pintype "bidirectional"))
      (node (ref "R23") (pin "1") (pinfunction "1_1") (pintype "passive"))
      (node (ref "R24") (pin "1") (pinfunction "1_1") (pintype "passive"))
    )
    (net (code "139") (name "SPI1_MISO") (class "Default")
      (node (ref "U$1") (pin "35") (pinfunction "SO/WR/EN_35") (pintype "bidirectional"))
      (node (ref "U2") (pin "16") (pinfunction "PA6_16") (pintype "bidirectional"))
    )
    (net (code "140") (name "SPI1_MOSI") (class "Default")
      (node (ref "U$1") (pin "36") (pinfunction "SI/RD/~{RW}_36") (pintype "bidirectional"))
      (node (ref "U2") (pin "17") (pinfunction "PA7_17") (pintype "bidirectional"))
    )
    (net (code "141") (name "SPI1_SCK") (class "Default")
      (node (ref "U$1") (pin "37") (pinfunction "SCK/AL_37") (pintype "bidirectional"))
      (node (ref "U2") (pin "15") (pinfunction "PA5_15") (pintype "bidirectional"))
    )
    (net (code "142") (name "SPI1_SS1_ETH1") (class "Default")
      (node (ref "U$1") (pin "34") (pinfunction "CS/~{CS}_34") (pintype "bidirectional"))
      (node (ref "U2") (pin "18") (pinfunction "PB0_18") (pintype "bidirectional"))
    )
    (net (code "143") (name "SPI2_MISO") (class "Default")
      (node (ref "U$3") (pin "35") (pinfunction "SO/WR/EN_35") (pintype "bidirectional"))
      (node (ref "U2") (pin "27") (pinfunction "PB14_27") (pintype "bidirectional"))
      (node (ref "U5") (pin "2") (pinfunction "SO_(IO1)_2") (pintype "output"))
    )
    (net (code "144") (name "SPI2_MOSI") (class "Default")
      (node (ref "U$3") (pin "36") (pinfunction "SI/RD/~{RW}_36") (pintype "bidirectional"))
      (node (ref "U2") (pin "28") (pinfunction "PB15_28") (pintype "bidirectional"))
      (node (ref "U5") (pin "5") (pinfunction "SI_(IO0)_5") (pintype "bidirectional"))
    )
    (net (code "145") (name "SPI2_SCK") (class "Default")
      (node (ref "U$3") (pin "37") (pinfunction "SCK/AL_37") (pintype "bidirectional"))
      (node (ref "U2") (pin "26") (pinfunction "PB13_26") (pintype "bidirectional"))
      (node (ref "U5") (pin "6") (pinfunction "CLK_6") (pintype "input"))
    )
    (net (code "146") (name "SPI2_SS1_ETH2") (class "Default")
      (node (ref "U$3") (pin "34") (pinfunction "CS/~{CS}_34") (pintype "bidirectional"))
      (node (ref "U2") (pin "29") (pinfunction "PA8_29") (pintype "bidirectional"))
    )
    (net (code "147") (name "SPI2_SS2_FLASH") (class "Default")
      (node (ref "U2") (pin "25") (pinfunction "PB12_25") (pintype "bidirectional"))
      (node (ref "U5") (pin "1") (pinfunction "CS_1") (pintype "input"))
    )
    (net (code "148") (name "SW0") (class "Default")
      (node (ref "S1") (pin "1") (pinfunction "1_1") (pintype "passive"))
      (node (ref "S1") (pin "2") (pinfunction "2_2") (pintype "passive"))
      (node (ref "U$5") (pin "2") (pinfunction "PF0/OSC_IN_2") (pintype "bidirectional"))
    )
    (net (code "149") (name "SW1") (class "Default")
      (node (ref "S2") (pin "1") (pinfunction "1_1") (pintype "passive"))
      (node (ref "S2") (pin "2") (pinfunction "2_2") (pintype "passive"))
      (node (ref "U$5") (pin "3") (pinfunction "PF1/OSC_OUT_3") (pintype "bidirectional"))
    )
    (net (code "150") (name "SWDCLK") (class "Default")
      (node (ref "JP25") (pin "2") (pinfunction "2_2") (pintype "passive"))
      (node (ref "U2") (pin "37") (pinfunction "PA14_37") (pintype "bidirectional"))
    )
    (net (code "151") (name "SWDIO") (class "Default")
      (node (ref "JP25") (pin "3") (pinfunction "3_3") (pintype "passive"))
      (node (ref "U2") (pin "34") (pinfunction "PA13_34") (pintype "bidirectional"))
    )
    (net (code "152") (name "TX1+") (class "Default")
      (node (ref "J4") (pin "TD+") (pinfunction "TD+_TD+") (pintype "bidirectional"))
      (node (ref "R12") (pin "1") (pinfunction "1_1") (pintype "passive"))
      (node (ref "U$1") (pin "20") (pinfunction "TPOUT+_20") (pintype "bidirectional"))
    )
    (net (code "153") (name "TX1-") (class "Default")
      (node (ref "J4") (pin "TD-") (pinfunction "TD-_TD-") (pintype "bidirectional"))
      (node (ref "R13") (pin "1") (pinfunction "1_1") (pintype "passive"))
      (node (ref "U$1") (pin "21") (pinfunction "TPOUT-_21") (pintype "bidirectional"))
    )
    (net (code "154") (name "TX1_CT") (class "Default")
      (node (ref "C29") (pin "1") (pinfunction "1_1") (pintype "passive"))
      (node (ref "J4") (pin "P4") (pinfunction "P4_P4") (pintype "bidirectional"))
      (node (ref "R16") (pin "1") (pinfunction "1_1") (pintype "passive"))
    )
    (net (code "155") (name "TX2+") (class "Default")
      (node (ref "J2") (pin "TD+") (pinfunction "TD+_TD+") (pintype "bidirectional"))
      (node (ref "R21") (pin "1") (pinfunction "1_1") (pintype "passive"))
      (node (ref "U$3") (pin "20") (pinfunction "TPOUT+_20") (pintype "bidirectional"))
    )
    (net (code "156") (name "TX2-") (class "Default")
      (node (ref "J2") (pin "TD-") (pinfunction "TD-_TD-") (pintype "bidirectional"))
      (node (ref "R22") (pin "1") (pinfunction "1_1") (pintype "passive"))
      (node (ref "U$3") (pin "21") (pinfunction "TPOUT-_21") (pintype "bidirectional"))
    )
    (net (code "157") (name "TX2_CT") (class "Default")
      (node (ref "C41") (pin "1") (pinfunction "1_1") (pintype "passive"))
      (node (ref "J2") (pin "P4") (pinfunction "P4_P4") (pintype "bidirectional"))
      (node (ref "R25") (pin "1") (pinfunction "1_1") (pintype "passive"))
    )
    (net (code "158") (name "UART_RX1") (class "Default")
      (node (ref "JP1") (pin "2") (pinfunction "2_2") (pintype "passive"))
      (node (ref "U1") (pin "1") (pinfunction "RO_1") (pintype "bidirectional"))
      (node (ref "U2") (pin "22") (pinfunction "PB11_22") (pintype "bidirectional"))
    )
    (net (code "159") (name "UART_RX2") (class "Default")
      (node (ref "JP7") (pin "2") (pinfunction "2_2") (pintype "passive"))
      (node (ref "U2") (pin "31") (pinfunction "PA10_31") (pintype "bidirectional"))
      (node (ref "U4") (pin "12") (pinfunction "R1OUT_12") (pintype "output"))
    )
    (net (code "160") (name "UART_TX1") (class "Default")
      (node (ref "JP1") (pin "3") (pinfunction "3_3") (pintype "passive"))
      (node (ref "U1") (pin "4") (pinfunction "DI_4") (pintype "bidirectional"))
      (node (ref "U2") (pin "21") (pinfunction "PB10_21") (pintype "bidirectional"))
    )
    (net (code "161") (name "UART_TX2") (class "Default")
      (node (ref "JP7") (pin "3") (pinfunction "3_3") (pintype "passive"))
      (node (ref "U2") (pin "30") (pinfunction "PA9_30") (pintype "bidirectional"))
      (node (ref "U4") (pin "11") (pinfunction "T1IN_11") (pintype "input"))
    )
    (net (code "162") (name "USB_D+") (class "Default")
      (node (ref "R45") (pin "1") (pinfunction "1_1") (pintype "passive"))
      (node (ref "R6") (pin "1") (pinfunction "1_1") (pintype "passive"))
      (node (ref "U2") (pin "33") (pinfunction "PA12_33") (pintype "bidirectional"))
    )
    (net (code "163") (name "USB_D-") (class "Default")
      (node (ref "R5") (pin "1") (pinfunction "1_1") (pintype "passive"))
      (node (ref "U2") (pin "32") (pinfunction "PA11_32") (pintype "power_in"))
    )
    (net (code "164") (name "VBAT") (class "Default")
      (node (ref "D5") (pin "3") (pinfunction "C_3") (pintype "passive"))
      (node (ref "U2") (pin "1") (pinfunction "VBAT_1") (pintype "input"))
    )
    (net (code "165") (name "VCOM") (class "Default")
      (node (ref "C3") (pin "1") (pinfunction "1_1") (pintype "passive"))
      (node (ref "DC1") (pin "3") (pinfunction "-VOUT_3") (pintype "passive"))
      (node (ref "JP10") (pin "2") (pinfunction "2_2") (pintype "passive"))
      (node (ref "JP13") (pin "2") (pinfunction "2_2") (pintype "passive"))
      (node (ref "JP14") (pin "2") (pinfunction "2_2") (pintype "passive"))
      (node (ref "JP15") (pin "2") (pinfunction "2_2") (pintype "passive"))
      (node (ref "JP16") (pin "2") (pinfunction "2_2") (pintype "passive"))
      (node (ref "JP17") (pin "2") (pinfunction "2_2") (pintype "passive"))
      (node (ref "JP18") (pin "2") (pinfunction "2_2") (pintype "passive"))
      (node (ref "JP19") (pin "2") (pinfunction "2_2") (pintype "passive"))
    )
    (net (code "166") (name "VIN") (class "Default")
      (node (ref "C3") (pin "2") (pinfunction "2_2") (pintype "passive"))
      (node (ref "L2") (pin "2") (pinfunction "2_2") (pintype "passive"))
      (node (ref "R3") (pin "1") (pinfunction "1_1") (pintype "passive"))
      (node (ref "R33") (pin "1") (pinfunction "1_1") (pintype "passive"))
      (node (ref "R35") (pin "1") (pinfunction "1_1") (pintype "passive"))
      (node (ref "R37") (pin "1") (pinfunction "1_1") (pintype "passive"))
      (node (ref "R49") (pin "1") (pinfunction "1_1") (pintype "passive"))
      (node (ref "R51") (pin "1") (pinfunction "1_1") (pintype "passive"))
      (node (ref "R53") (pin "1") (pinfunction "1_1") (pintype "passive"))
      (node (ref "R55") (pin "1") (pinfunction "1_1") (pintype "passive"))
    )
    (net (code "167") (name "VIN1") (class "Default")
      (node (ref "C15") (pin "+") (pinfunction "+_+") (pintype "passive"))
      (node (ref "D8") (pin "C") (pinfunction "C_C") (pintype "passive"))
      (node (ref "R7") (pin "2") (pinfunction "2_2") (pintype "passive"))
      (node (ref "U3") (pin "6") (pinfunction "VCC_6") (pintype "bidirectional"))
    )
    (net (code "168") (name "VIN2") (class "Default")
      (node (ref "R7") (pin "1") (pinfunction "1_1") (pintype "passive"))
      (node (ref "U3") (pin "1") (pinfunction "SWC_1") (pintype "bidirectional"))
      (node (ref "U3") (pin "7") (pinfunction "SEN_7") (pintype "bidirectional"))
      (node (ref "U3") (pin "8") (pinfunction "DVR_8") (pintype "bidirectional"))
    )
    (net (code "169") (name "unconnected-(IC5-DNC-Pad3)") (class "Default")
      (node (ref "IC5") (pin "3") (pinfunction "DNC_3") (pintype "no_connect"))
    )
    (net (code "170") (name "unconnected-(IC5-DNC-Pad4)") (class "Default")
      (node (ref "IC5") (pin "4") (pinfunction "DNC_4") (pintype "no_connect"))
    )
    (net (code "171") (name "unconnected-(J2-PadNC)") (class "Default")
      (node (ref "J2") (pin "NC") (pinfunction "NC_NC") (pintype "bidirectional"))
    )
    (net (code "172") (name "unconnected-(J4-PadNC)") (class "Default")
      (node (ref "J4") (pin "NC") (pinfunction "NC_NC") (pintype "bidirectional"))
    )
    (net (code "173") (name "unconnected-(JP3-PadVBUS)") (class "Default")
      (node (ref "JP3") (pin "VBUS") (pinfunction "VBUS_VBUS") (pintype "bidirectional"))
    )
    (net (code "174") (name "unconnected-(JP12-Pad4)") (class "Default")
      (node (ref "JP12") (pin "4") (pinfunction "4_4") (pintype "passive"))
    )
    (net (code "175") (name "unconnected-(JP12-Pad6)") (class "Default")
      (node (ref "JP12") (pin "6") (pinfunction "6_6") (pintype "passive"))
    )
    (net (code "176") (name "unconnected-(JP12-Pad9)") (class "Default")
      (node (ref "JP12") (pin "9") (pinfunction "9_9") (pintype "passive"))
    )
    (net (code "177") (name "unconnected-(JP12-Pad10)") (class "Default")
      (node (ref "JP12") (pin "10") (pinfunction "10_10") (pintype "passive"))
    )
    (net (code "178") (name "unconnected-(U$1-AD0-Pad38)") (class "Default")
      (node (ref "U$1") (pin "38") (pinfunction "AD0_38") (pintype "bidirectional"))
    )
    (net (code "179") (name "unconnected-(U$1-AD1-Pad39)") (class "Default")
      (node (ref "U$1") (pin "39") (pinfunction "AD1_39") (pintype "bidirectional"))
    )
    (net (code "180") (name "unconnected-(U$1-AD2-Pad40)") (class "Default")
      (node (ref "U$1") (pin "40") (pinfunction "AD2_40") (pintype "bidirectional"))
    )
    (net (code "181") (name "unconnected-(U$1-AD3-Pad41)") (class "Default")
      (node (ref "U$1") (pin "41") (pinfunction "AD3_41") (pintype "bidirectional"))
    )
    (net (code "182") (name "unconnected-(U$1-AD4-Pad5)") (class "Default")
      (node (ref "U$1") (pin "5") (pinfunction "AD4_5") (pintype "bidirectional"))
    )
    (net (code "183") (name "unconnected-(U$1-AD5-Pad6)") (class "Default")
      (node (ref "U$1") (pin "6") (pinfunction "AD5_6") (pintype "bidirectional"))
    )
    (net (code "184") (name "unconnected-(U$1-AD6-Pad7)") (class "Default")
      (node (ref "U$1") (pin "7") (pinfunction "AD6_7") (pintype "bidirectional"))
    )
    (net (code "185") (name "unconnected-(U$1-AD7-Pad8)") (class "Default")
      (node (ref "U$1") (pin "8") (pinfunction "AD7_8") (pintype "bidirectional"))
    )
    (net (code "186") (name "unconnected-(U$1-AD8-Pad25)") (class "Default")
      (node (ref "U$1") (pin "25") (pinfunction "AD8_25") (pintype "bidirectional"))
    )
    (net (code "187") (name "unconnected-(U$1-AD9-Pad26)") (class "Default")
      (node (ref "U$1") (pin "26") (pinfunction "AD9_26") (pintype "bidirectional"))
    )
    (net (code "188") (name "unconnected-(U$1-AD10-Pad27)") (class "Default")
      (node (ref "U$1") (pin "27") (pinfunction "AD10_27") (pintype "bidirectional"))
    )
    (net (code "189") (name "unconnected-(U$1-AD11-Pad28)") (class "Default")
      (node (ref "U$1") (pin "28") (pinfunction "AD11_28") (pintype "bidirectional"))
    )
    (net (code "190") (name "unconnected-(U$1-AD12-Pad29)") (class "Default")
      (node (ref "U$1") (pin "29") (pinfunction "AD12_29") (pintype "bidirectional"))
    )
    (net (code "191") (name "unconnected-(U$1-AD13-Pad30)") (class "Default")
      (node (ref "U$1") (pin "30") (pinfunction "AD13_30") (pintype "bidirectional"))
    )
    (net (code "192") (name "unconnected-(U$1-AD14-Pad31)") (class "Default")
      (node (ref "U$1") (pin "31") (pinfunction "AD14_31") (pintype "bidirectional"))
    )
    (net (code "193") (name "unconnected-(U$1-CLKOUT-Pad23)") (class "Default")
      (node (ref "U$1") (pin "23") (pinfunction "CLKOUT_23") (pintype "bidirectional"))
    )
    (net (code "194") (name "unconnected-(U$1-PSPCFG0-Pad32)") (class "Default")
      (node (ref "U$1") (pin "32") (pinfunction "PSPCFG0_32") (pintype "bidirectional"))
    )
    (net (code "195") (name "unconnected-(U$3-AD0-Pad38)") (class "Default")
      (node (ref "U$3") (pin "38") (pinfunction "AD0_38") (pintype "bidirectional"))
    )
    (net (code "196") (name "unconnected-(U$3-AD1-Pad39)") (class "Default")
      (node (ref "U$3") (pin "39") (pinfunction "AD1_39") (pintype "bidirectional"))
    )
    (net (code "197") (name "unconnected-(U$3-AD2-Pad40)") (class "Default")
      (node (ref "U$3") (pin "40") (pinfunction "AD2_40") (pintype "bidirectional"))
    )
    (net (code "198") (name "unconnected-(U$3-AD3-Pad41)") (class "Default")
      (node (ref "U$3") (pin "41") (pinfunction "AD3_41") (pintype "bidirectional"))
    )
    (net (code "199") (name "unconnected-(U$3-AD4-Pad5)") (class "Default")
      (node (ref "U$3") (pin "5") (pinfunction "AD4_5") (pintype "bidirectional"))
    )
    (net (code "200") (name "unconnected-(U$3-AD5-Pad6)") (class "Default")
      (node (ref "U$3") (pin "6") (pinfunction "AD5_6") (pintype "bidirectional"))
    )
    (net (code "201") (name "unconnected-(U$3-AD6-Pad7)") (class "Default")
      (node (ref "U$3") (pin "7") (pinfunction "AD6_7") (pintype "bidirectional"))
    )
    (net (code "202") (name "unconnected-(U$3-AD7-Pad8)") (class "Default")
      (node (ref "U$3") (pin "8") (pinfunction "AD7_8") (pintype "bidirectional"))
    )
    (net (code "203") (name "unconnected-(U$3-AD8-Pad25)") (class "Default")
      (node (ref "U$3") (pin "25") (pinfunction "AD8_25") (pintype "bidirectional"))
    )
    (net (code "204") (name "unconnected-(U$3-AD9-Pad26)") (class "Default")
      (node (ref "U$3") (pin "26") (pinfunction "AD9_26") (pintype "bidirectional"))
    )
    (net (code "205") (name "unconnected-(U$3-AD10-Pad27)") (class "Default")
      (node (ref "U$3") (pin "27") (pinfunction "AD10_27") (pintype "bidirectional"))
    )
    (net (code "206") (name "unconnected-(U$3-AD11-Pad28)") (class "Default")
      (node (ref "U$3") (pin "28") (pinfunction "AD11_28") (pintype "bidirectional"))
    )
    (net (code "207") (name "unconnected-(U$3-AD12-Pad29)") (class "Default")
      (node (ref "U$3") (pin "29") (pinfunction "AD12_29") (pintype "bidirectional"))
    )
    (net (code "208") (name "unconnected-(U$3-AD13-Pad30)") (class "Default")
      (node (ref "U$3") (pin "30") (pinfunction "AD13_30") (pintype "bidirectional"))
    )
    (net (code "209") (name "unconnected-(U$3-AD14-Pad31)") (class "Default")
      (node (ref "U$3") (pin "31") (pinfunction "AD14_31") (pintype "bidirectional"))
    )
    (net (code "210") (name "unconnected-(U$3-CLKOUT-Pad23)") (class "Default")
      (node (ref "U$3") (pin "23") (pinfunction "CLKOUT_23") (pintype "bidirectional"))
    )
    (net (code "211") (name "unconnected-(U$3-PSPCFG0-Pad32)") (class "Default")
      (node (ref "U$3") (pin "32") (pinfunction "PSPCFG0_32") (pintype "bidirectional"))
    )
    (net (code "212") (name "unconnected-(U$5-PA12-Pad22)") (class "Default")
      (node (ref "U$5") (pin "22") (pinfunction "PA12_22") (pintype "bidirectional"))
    )
    (net (code "213") (name "unconnected-(U2-PA0-WKUP-Pad10)") (class "Default")
      (node (ref "U2") (pin "10") (pinfunction "PA0-WKUP_10") (pintype "bidirectional"))
    )
    (net (code "214") (name "unconnected-(U2-PA1-Pad11)") (class "Default")
      (node (ref "U2") (pin "11") (pinfunction "PA1_11") (pintype "bidirectional"))
    )
    (net (code "215") (name "unconnected-(U2-PA4-Pad14)") (class "Default")
      (node (ref "U2") (pin "14") (pinfunction "PA4_14") (pintype "bidirectional"))
    )
    (net (code "216") (name "unconnected-(U2-PB3-Pad39)") (class "Default")
      (node (ref "U2") (pin "39") (pinfunction "PB3_39") (pintype "bidirectional"))
    )
    (net (code "217") (name "unconnected-(U2-PB4-Pad40)") (class "Default")
      (node (ref "U2") (pin "40") (pinfunction "PB4_40") (pintype "bidirectional"))
    )
    (net (code "218") (name "unconnected-(U2-PB5-Pad41)") (class "Default")
      (node (ref "U2") (pin "41") (pinfunction "PB5_41") (pintype "bidirectional"))
    )
    (net (code "219") (name "unconnected-(U2-PB8-Pad45)") (class "Default")
      (node (ref "U2") (pin "45") (pinfunction "PB8_45") (pintype "bidirectional"))
    )
    (net (code "220") (name "unconnected-(U2-PB9-Pad46)") (class "Default")
      (node (ref "U2") (pin "46") (pinfunction "PB9_46") (pintype "bidirectional"))
    )
    (net (code "221") (name "unconnected-(U2-PC13-TAMPER-RTC-Pad2)") (class "Default")
      (node (ref "U2") (pin "2") (pinfunction "PC13-TAMPER-RTC_2") (pintype "bidirectional"))
    )
    (net (code "222") (name "unconnected-(U4-R2IN-Pad8)") (class "Default")
      (node (ref "U4") (pin "8") (pinfunction "R2IN_8") (pintype "input"))
    )
    (net (code "223") (name "unconnected-(U4-R2OUT-Pad9)") (class "Default")
      (node (ref "U4") (pin "9") (pinfunction "R2OUT_9") (pintype "output"))
    )
    (net (code "224") (name "unconnected-(U4-T2IN-Pad10)") (class "Default")
      (node (ref "U4") (pin "10") (pinfunction "T2IN_10") (pintype "input"))
    )
    (net (code "225") (name "unconnected-(U4-T2OUT-Pad7)") (class "Default")
      (node (ref "U4") (pin "7") (pinfunction "T2OUT_7") (pintype "output"))
    )
    (net (code "226") (name "unconnected-(U5-HOLD_(IO3)-Pad7)") (class "Default")
      (node (ref "U5") (pin "7") (pinfunction "HOLD_(IO3)_7") (pintype "bidirectional"))
    )
    (net (code "227") (name "unconnected-(U5-WP_(IO2)-Pad3)") (class "Default")
      (node (ref "U5") (pin "3") (pinfunction "WP_(IO2)_3") (pintype "bidirectional"))
    )
    (net (code "228") (name "unconnected-(X1-Pad1)") (class "Default")
      (node (ref "X1") (pin "1") (pinfunction "1_1") (pintype "passive"))
    )
    (net (code "229") (name "unconnected-(X1-Pad4)") (class "Default")
      (node (ref "X1") (pin "4") (pinfunction "4_4") (pintype "passive"))
    )
    (net (code "230") (name "unconnected-(X1-Pad6)") (class "Default")
      (node (ref "X1") (pin "6") (pinfunction "6_6") (pintype "passive"))
    )
    (net (code "231") (name "unconnected-(X1-Pad7)") (class "Default")
      (node (ref "X1") (pin "7") (pinfunction "7_7") (pintype "passive"))
    )
    (net (code "232") (name "unconnected-(X1-Pad8)") (class "Default")
      (node (ref "X1") (pin "8") (pinfunction "8_8") (pintype "passive"))
    )
    (net (code "233") (name "unconnected-(X1-Pad9)") (class "Default")
      (node (ref "X1") (pin "9") (pinfunction "9_9") (pintype "passive"))
    )
  )
)
